# robot.net
KiCad netlist of a schematic drawn in Altium Designer
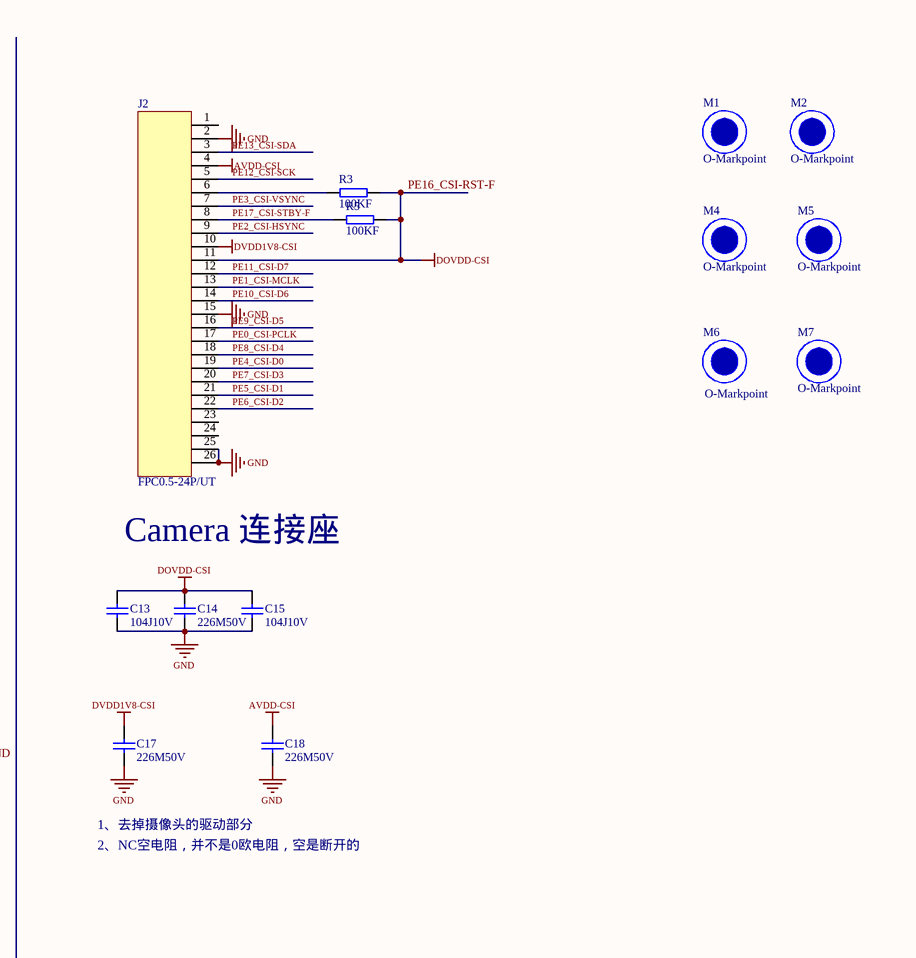
[diagram p0: robot.SchDoc, top right]
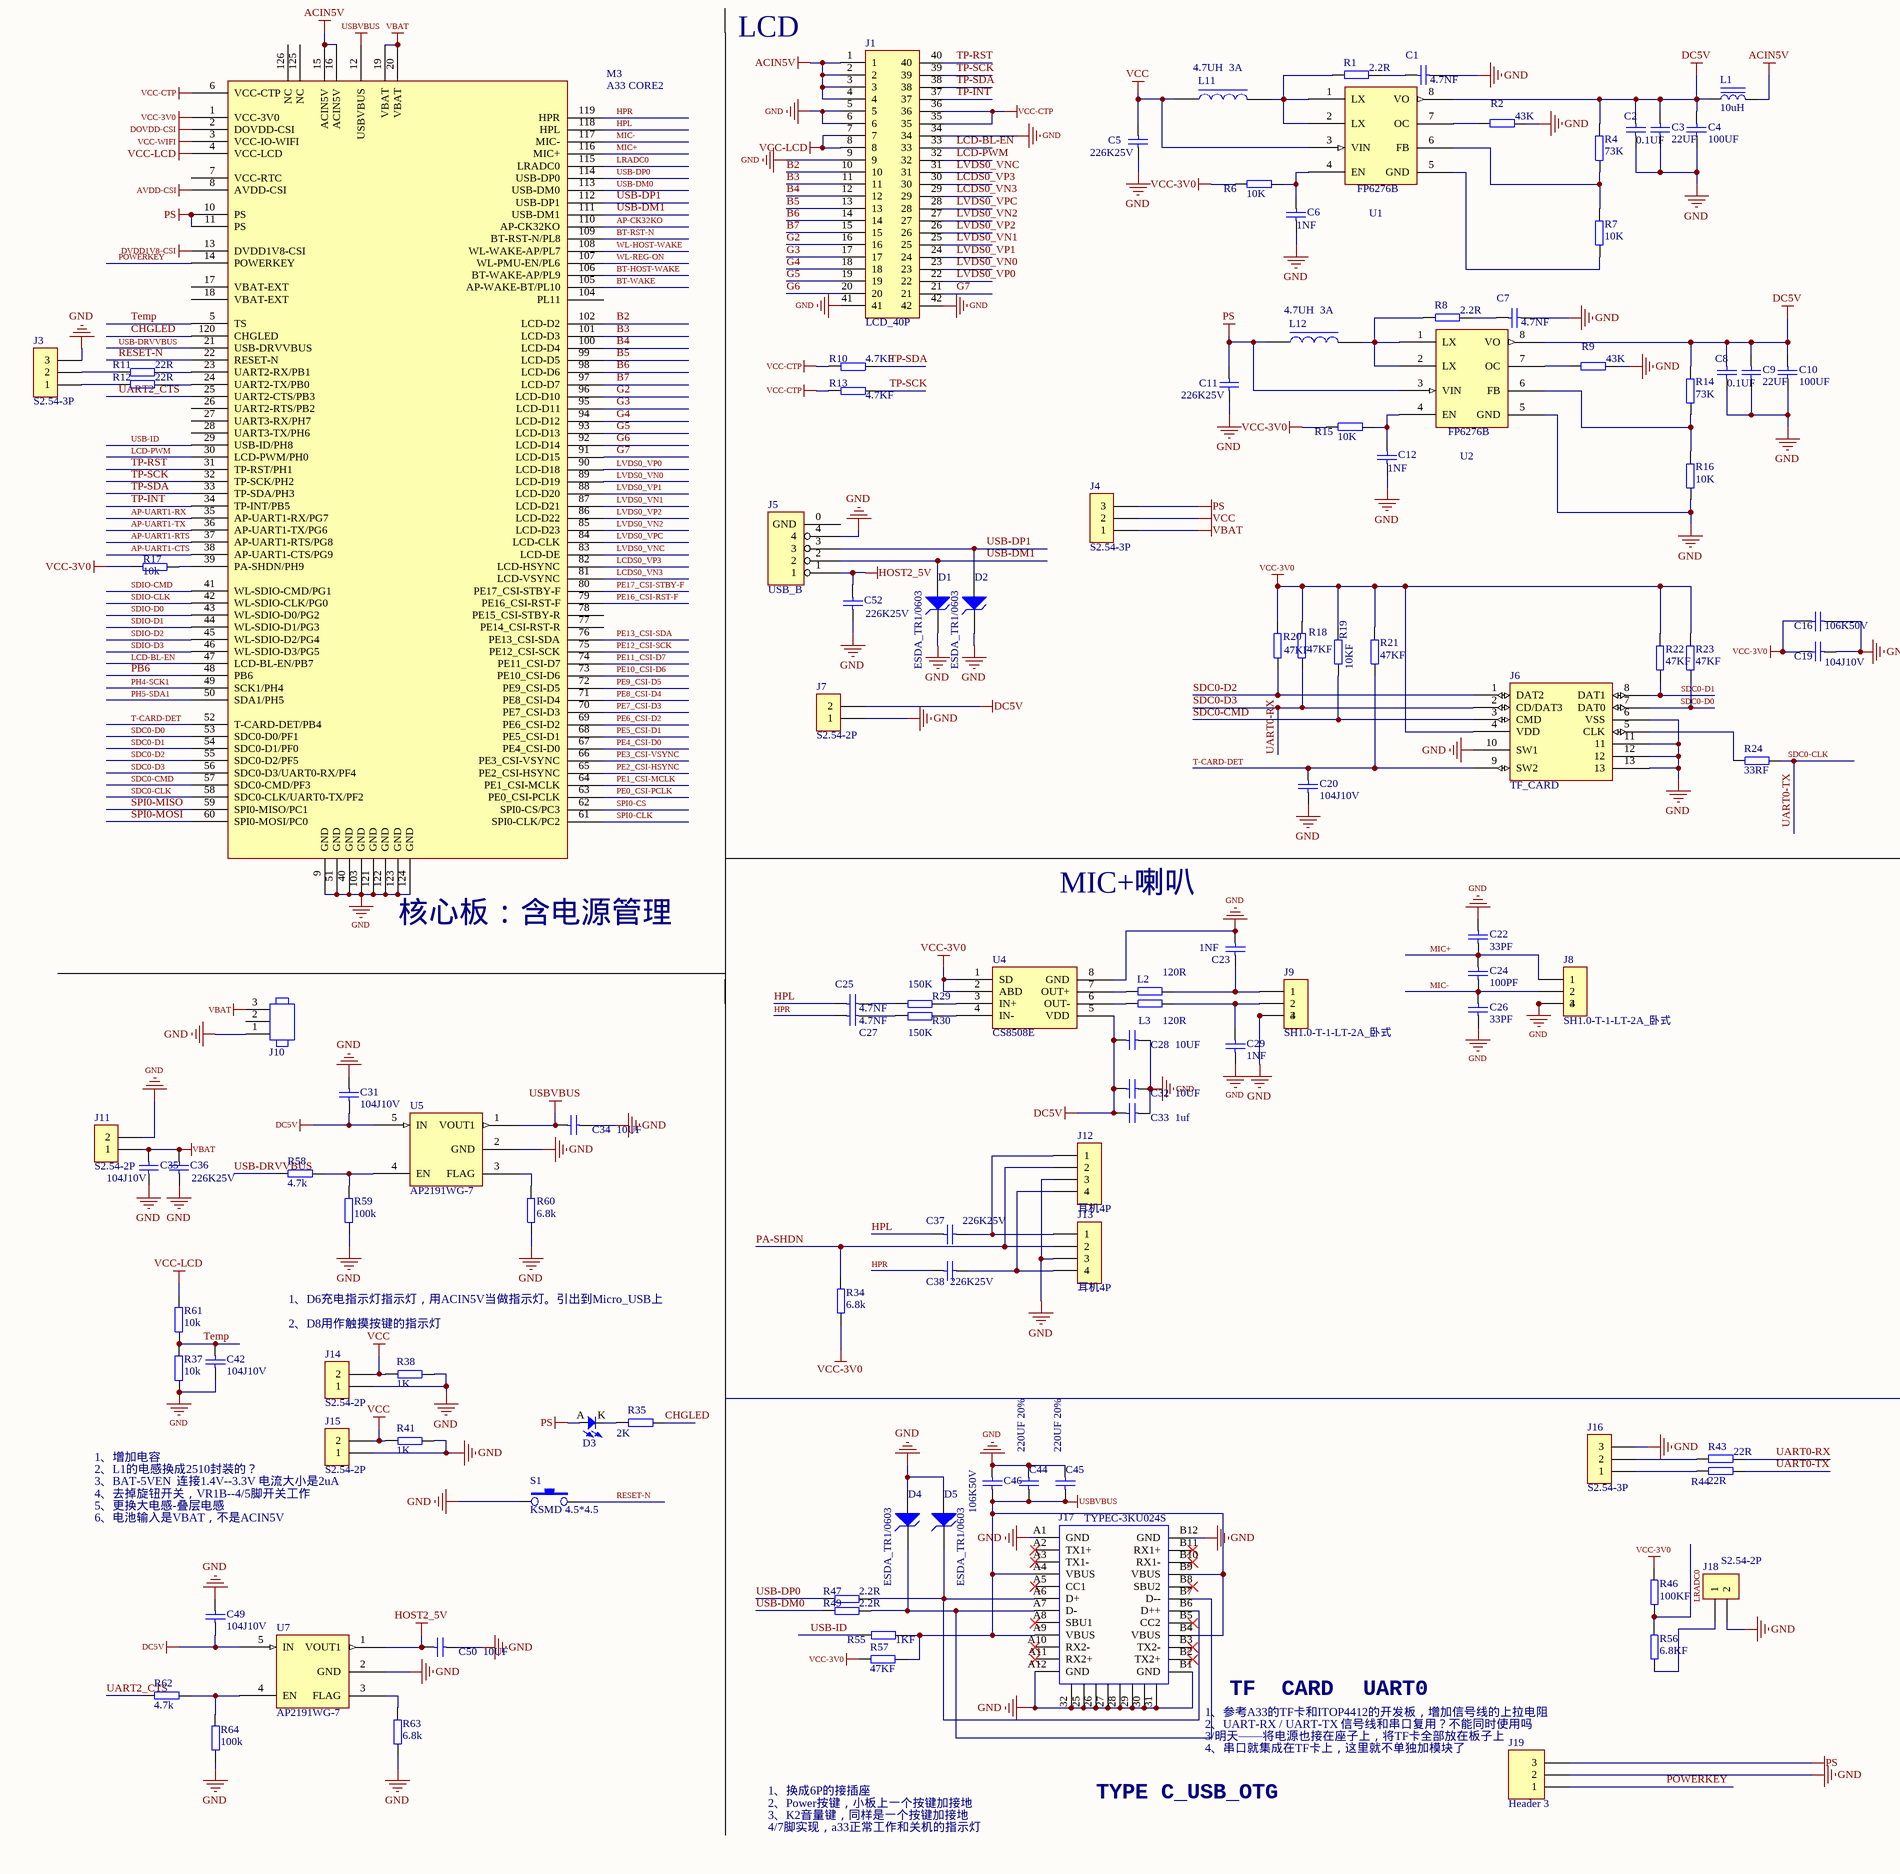
[diagram p1: robot.SchDoc, bottom left]
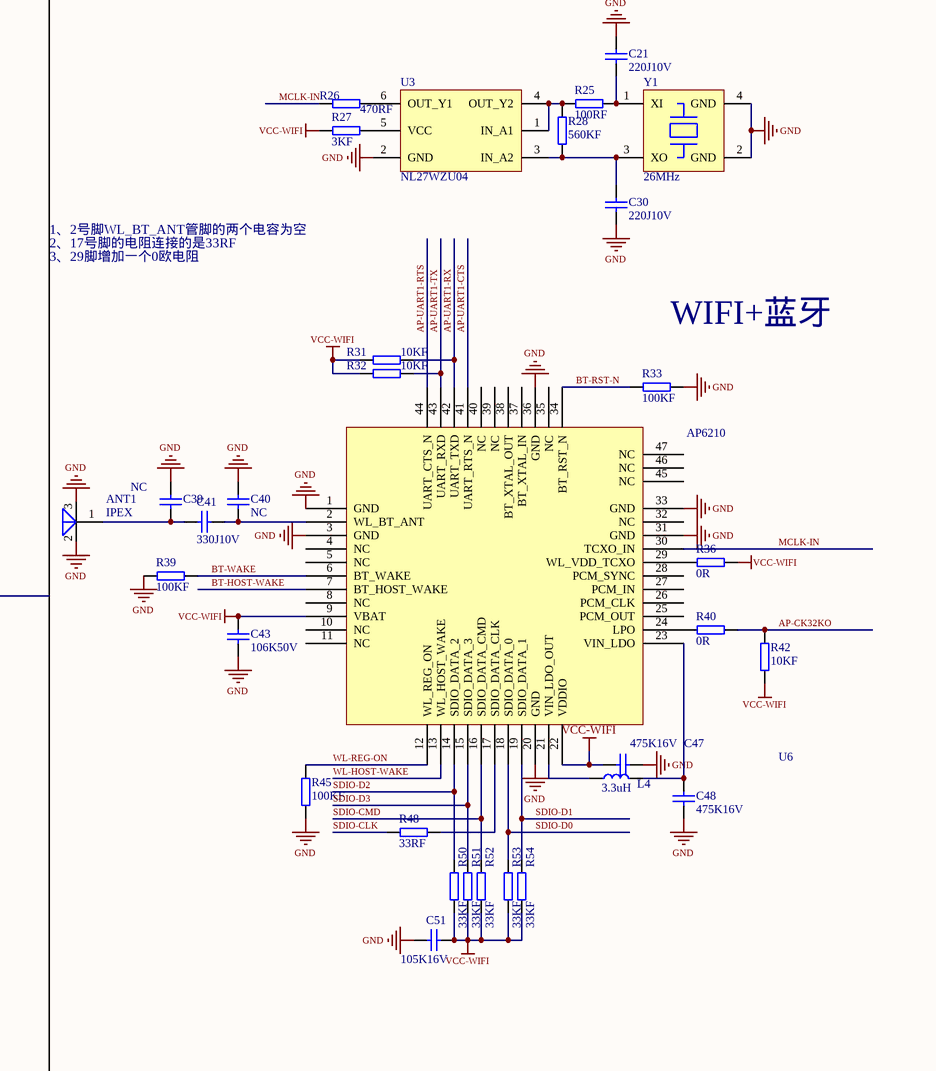
[diagram p2: robot.SchDoc, bottom right]

(export (version "E")
  (design (tool "Eeschema 10.0.6"))
  (components
    (comp (ref "ANT1")
      (value "IPEX")
      (footprint "J-IPEX")
      (description "天线接口IPEX")
      (libsource (lib "Connector") (part "J-IPEX"))
    )
    (comp (ref "C1")
      (value "4.7NF")
      (footprint "C0603")
      (description "贴片电容-陶瓷")
      (libsource (lib "Capacitor") (part "C0603X7R-330J25V"))
    )
    (comp (ref "C2")
      (value "0.1UF")
      (footprint "C0402")
      (description "贴片电容-陶瓷")
      (libsource (lib "AIWAC-bolsterV01") (part "C0402X7R-101J10V"))
    )
    (comp (ref "C3")
      (value "22UF")
      (footprint "C0603")
      (description "贴片电容-陶瓷")
      (libsource (lib "Capacitor") (part "C0603X7R-330J25V"))
    )
    (comp (ref "C4")
      (value "100UF")
      (footprint "CD3X5.3SMD")
      (description "贴片电容-陶瓷")
      (libsource (lib "Capacitor") (part "C0603X7R-330J25V"))
    )
    (comp (ref "C5")
      (value "226K25V")
      (footprint "C0805")
      (description "贴片电容-陶瓷")
      (libsource (lib "Capacitor") (part "C0805X7R-226K25V"))
    )
    (comp (ref "C6")
      (value "1NF")
      (footprint "C0402")
      (description "贴片电容-陶瓷")
      (libsource (lib "AIWAC-bolsterV01") (part "C0402X7R-101J10V"))
    )
    (comp (ref "C7")
      (value "4.7NF")
      (footprint "C0603")
      (description "贴片电容-陶瓷")
      (libsource (lib "Capacitor") (part "C0603X7R-330J25V"))
    )
    (comp (ref "C8")
      (value "0.1UF")
      (footprint "C0402")
      (description "贴片电容-陶瓷")
      (libsource (lib "AIWAC-bolsterV01") (part "C0402X7R-101J10V"))
    )
    (comp (ref "C9")
      (value "22UF")
      (footprint "C0603")
      (description "贴片电容-陶瓷")
      (libsource (lib "Capacitor") (part "C0603X7R-330J25V"))
    )
    (comp (ref "C10")
      (value "100UF")
      (footprint "CD3X5.3SMD")
      (description "贴片电容-陶瓷")
      (libsource (lib "Capacitor") (part "C0603X7R-330J25V"))
    )
    (comp (ref "C11")
      (value "226K25V")
      (footprint "C0805")
      (description "贴片电容-陶瓷")
      (libsource (lib "Capacitor") (part "C0805X7R-226K25V"))
    )
    (comp (ref "C12")
      (value "1NF")
      (footprint "C0402")
      (description "贴片电容-陶瓷")
      (libsource (lib "AIWAC-bolsterV01") (part "C0402X7R-101J10V"))
    )
    (comp (ref "C13")
      (value "104J10V")
      (footprint "C0402")
      (description "贴片电容-陶瓷")
      (libsource (lib "Capacitor") (part "C0402X7R-104J10V"))
    )
    (comp (ref "C14")
      (value "226M50V")
      (footprint "C0805")
      (description "贴片电容-陶瓷")
      (libsource (lib "Capacitor") (part "C0805Y5V-226M50V"))
    )
    (comp (ref "C15")
      (value "104J10V")
      (footprint "C0402")
      (description "贴片电容-陶瓷")
      (libsource (lib "Capacitor") (part "C0402X7R-104J10V"))
    )
    (comp (ref "C16")
      (value "106K50V")
      (footprint "C0603")
      (description "贴片电容-陶瓷")
      (libsource (lib "Capacitor") (part "C0603X7R-106K50V"))
    )
    (comp (ref "C17")
      (value "226M50V")
      (footprint "C0805")
      (description "贴片电容-陶瓷")
      (libsource (lib "Capacitor") (part "C0805Y5V-226M50V"))
    )
    (comp (ref "C18")
      (value "226M50V")
      (footprint "C0805")
      (description "贴片电容-陶瓷")
      (libsource (lib "Capacitor") (part "C0805Y5V-226M50V"))
    )
    (comp (ref "C19")
      (value "104J10V")
      (footprint "C0402")
      (description "贴片电容-陶瓷")
      (libsource (lib "Capacitor") (part "C0402X7R-104J10V"))
    )
    (comp (ref "C20")
      (value "104J10V")
      (footprint "C0402")
      (description "贴片电容-陶瓷")
      (libsource (lib "Capacitor") (part "C0402X7R-104J10V"))
    )
    (comp (ref "C21")
      (value "220J10V")
      (footprint "C0402")
      (description "贴片电容-陶瓷")
      (libsource (lib "Capacitor") (part "C0402X7R-220J10V"))
    )
    (comp (ref "C22")
      (value "33PF")
      (footprint "C0402")
      (description "贴片电容-陶瓷")
      (libsource (lib "Capacitor") (part "C0402X7R-104J10V"))
    )
    (comp (ref "C23")
      (value "1NF")
      (footprint "C0402")
      (description "贴片电容-陶瓷")
      (libsource (lib "Capacitor") (part "C0402X7R-220J10V"))
    )
    (comp (ref "C24")
      (value "100PF")
      (footprint "C0402")
      (description "贴片电容-陶瓷")
      (libsource (lib "Capacitor") (part "C0402X7R-104J10V"))
    )
    (comp (ref "C25")
      (value "4.7NF")
      (footprint "C0603")
      (description "贴片电容-陶瓷")
      (libsource (lib "Capacitor") (part "C0603X7R-330J25V"))
    )
    (comp (ref "C26")
      (value "33PF")
      (footprint "C0402")
      (description "贴片电容-陶瓷")
      (libsource (lib "Capacitor") (part "C0402X7R-104J10V"))
    )
    (comp (ref "C27")
      (value "4.7NF")
      (footprint "C0603")
      (description "贴片电容-陶瓷")
      (libsource (lib "Capacitor") (part "C0603X7R-330J25V"))
    )
    (comp (ref "C28")
      (value "10UF")
      (footprint "C0603")
      (description "贴片电容-陶瓷")
      (libsource (lib "Capacitor") (part "C0603X7R-330J25V"))
    )
    (comp (ref "C29")
      (value "1NF")
      (footprint "C0402")
      (description "贴片电容-陶瓷")
      (libsource (lib "Capacitor") (part "C0402X7R-220J10V"))
    )
    (comp (ref "C30")
      (value "220J10V")
      (footprint "C0402")
      (description "贴片电容-陶瓷")
      (libsource (lib "Capacitor") (part "C0402X7R-220J10V"))
    )
    (comp (ref "C31")
      (value "104J10V")
      (footprint "C0402")
      (description "贴片电容-陶瓷")
      (libsource (lib "Capacitor") (part "C0402X7R-104J10V"))
    )
    (comp (ref "C32")
      (value "10UF")
      (footprint "C0603")
      (description "贴片电容-陶瓷")
      (libsource (lib "Capacitor") (part "C0603X7R-330J25V"))
    )
    (comp (ref "C33")
      (value "1uf")
      (footprint "C0603")
      (description "贴片电容-陶瓷")
      (libsource (lib "Capacitor") (part "C0603X7R-330J25V"))
    )
    (comp (ref "C34")
      (value "10UF")
      (footprint "C0603")
      (description "贴片电容-陶瓷")
      (libsource (lib "Capacitor") (part "C0603X7R-330J25V"))
    )
    (comp (ref "C35")
      (value "104J10V")
      (footprint "C0402")
      (description "贴片电容-陶瓷")
      (libsource (lib "Capacitor") (part "C0402X7R-104J10V"))
    )
    (comp (ref "C36")
      (value "226K25V")
      (footprint "C0805")
      (description "贴片电容-陶瓷")
      (libsource (lib "Capacitor") (part "C0805X7R-226K25V"))
    )
    (comp (ref "C37")
      (value "226K25V")
      (footprint "C0805")
      (description "贴片电容-陶瓷")
      (libsource (lib "Capacitor") (part "C0805X7R-226K25V"))
    )
    (comp (ref "C38")
      (value "226K25V")
      (footprint "C0805")
      (description "贴片电容-陶瓷")
      (libsource (lib "Capacitor") (part "C0805X7R-226K25V"))
    )
    (comp (ref "C39")
      (value "NC")
      (footprint "C0402")
      (description "贴片电容-陶瓷")
      (libsource (lib "Capacitor") (part "C0402X7R-220J10V"))
    )
    (comp (ref "C40")
      (value "NC")
      (footprint "C0402")
      (description "贴片电容-陶瓷")
      (libsource (lib "Capacitor") (part "C0402X7R-220J10V"))
    )
    (comp (ref "C41")
      (value "330J10V")
      (footprint "C0402")
      (description "贴片电容-陶瓷")
      (libsource (lib "Capacitor") (part "C0402X7R-330J10V"))
    )
    (comp (ref "C42")
      (value "104J10V")
      (footprint "C0402")
      (description "贴片电容-陶瓷")
      (libsource (lib "Capacitor") (part "C0402X7R-104J10V"))
    )
    (comp (ref "C43")
      (value "106K50V")
      (footprint "C0603")
      (description "贴片电容-陶瓷")
      (libsource (lib "Capacitor") (part "C0603X7R-106K50V"))
    )
    (comp (ref "C44")
      (value "220UF 20%")
      (footprint "C1206")
      (description "C 1206钽电容 --220UF 10V 3216 A型 有极性电容 3.2mm X 1.6mm")
      (libsource (lib "Capacitor") (part "C1206-A型 极性电容"))
    )
    (comp (ref "C45")
      (value "220UF 20%")
      (footprint "C1206")
      (description "C 1206钽电容 --220UF 10V 3216 A型 有极性电容 3.2mm X 1.6mm")
      (libsource (lib "Capacitor") (part "C1206-A型 极性电容"))
    )
    (comp (ref "C46")
      (value "106K50V")
      (footprint "C0603")
      (description "贴片电容-陶瓷")
      (libsource (lib "Capacitor") (part "C0603X7R-106K50V"))
    )
    (comp (ref "C47")
      (value "475K16V")
      (footprint "C0603")
      (description "贴片电容-陶瓷")
      (libsource (lib "Capacitor") (part "C0603X7R-475K16V"))
    )
    (comp (ref "C48")
      (value "475K16V")
      (footprint "C0603")
      (description "贴片电容-陶瓷")
      (libsource (lib "Capacitor") (part "C0603X7R-475K16V"))
    )
    (comp (ref "C49")
      (value "104J10V")
      (footprint "C0402")
      (description "贴片电容-陶瓷")
      (libsource (lib "Capacitor") (part "C0402X7R-104J10V"))
    )
    (comp (ref "C50")
      (value "10UF")
      (footprint "C0603")
      (description "贴片电容-陶瓷")
      (libsource (lib "Capacitor") (part "C0603X7R-330J25V"))
    )
    (comp (ref "C51")
      (value "105K16V")
      (footprint "C0603")
      (description "贴片电容-陶瓷")
      (libsource (lib "Capacitor") (part "C0603X7R-105K16V"))
    )
    (comp (ref "C52")
      (value "226K25V")
      (footprint "C0805")
      (description "贴片电容-陶瓷")
      (libsource (lib "Capacitor") (part "C0805X7R-226K25V"))
    )
    (comp (ref "D1")
      (value "ESDA_TR1/0603")
      (footprint "HS_0603D")
      (description "Zener Diode")
      (fields (field (name "PUBLISHER") "*"))
      (libsource (lib "1_1") (part "D Zener"))
    )
    (comp (ref "D2")
      (value "ESDA_TR1/0603")
      (footprint "HS_0603D")
      (description "Zener Diode")
      (fields (field (name "PUBLISHER") "*"))
      (libsource (lib "1_1") (part "D Zener"))
    )
    (comp (ref "D3") (value "发光二极管") (footprint "LED 3MM") (libsource (lib "PCB_Project_2") (part "发光二极管")))
    (comp (ref "D4")
      (value "ESDA_TR1/0603")
      (footprint "HS_0603D")
      (description "Zener Diode")
      (fields (field (name "PUBLISHER") "*"))
      (libsource (lib "1_1") (part "D Zener"))
    )
    (comp (ref "D5")
      (value "ESDA_TR1/0603")
      (footprint "HS_0603D")
      (description "Zener Diode")
      (fields (field (name "PUBLISHER") "*"))
      (libsource (lib "1_1") (part "D Zener"))
    )
    (comp (ref "J1") (value "LCD_40P") (footprint "LCD P40") (libsource (lib "Connector") (part "LCD_40P")))
    (comp (ref "J2")
      (value "FPC0.5-24P/UT")
      (footprint "FPC0.5-24P/UT")
      (description "FPC端子")
      (libsource (lib "Connector") (part "J-FPC0.5-24P/UT"))
    )
    (comp (ref "J3")
      (value "S2.54-3P")
      (footprint "S2.54-3P")
      (description "单排排针-直针")
      (libsource (lib "PCB_Project") (part "J-S2.54-3P"))
    )
    (comp (ref "J4")
      (value "S2.54-3P")
      (footprint "S2.54-3P")
      (description "单排排针-直针")
      (libsource (lib "PCB_Project") (part "J-S2.54-3P"))
    )
    (comp (ref "J5")
      (value "USB_B")
      (footprint "PCB1:SMD USB A型")
      (libsource (lib "XU-GENARAL SCH") (part "USB_B"))
    )
    (comp (ref "J6")
      (value "TF_CARD")
      (footprint "SD_CARD_7")
      (description "MS110-C10B-C16")
      (libsource (lib "Connector") (part "TF_CARD"))
    )
    (comp (ref "J7")
      (value "S2.54-2P")
      (footprint "J-SH2.0-T-1-LT-2A_立式")
      (description "单排排针-直针")
      (libsource (lib "Sheye-Connector") (part "J-S2.54-2P"))
    )
    (comp (ref "J8")
      (value "SH1.0-T-1-LT-2A_卧式")
      (footprint "J-SH1.27-2")
      (libsource (lib "Connector") (part "SH1.0-T-1-LT-2A_卧式"))
    )
    (comp (ref "J9")
      (value "SH1.0-T-1-LT-2A_卧式")
      (footprint "J-SH1.27-2")
      (libsource (lib "Connector") (part "SH1.0-T-1-LT-2A_卧式"))
    )
    (comp (ref "J10") (value "SW") (footprint "拨码开关") (libsource (lib "XU-GENARAL SCH") (part "卡槽-3")))
    (comp (ref "J11")
      (value "S2.54-2P")
      (footprint "J-SH2.0-T-1-LT-2A_立式")
      (description "单排排针-直针")
      (libsource (lib "Sheye-Connector") (part "J-S2.54-2P"))
    )
    (comp (ref "J12")
      (value "耳机4P")
      (footprint "耳机接口")
      (description "单排排针-直针")
      (libsource (lib "Connector") (part "J-S2.54-4P"))
    )
    (comp (ref "J13")
      (value "耳机4P")
      (footprint "耳机接口")
      (description "单排排针-直针")
      (libsource (lib "Connector") (part "J-S2.54-4P"))
    )
    (comp (ref "J14")
      (value "S2.54-2P")
      (footprint "J-SH2.0-T-1-LT-2A_立式")
      (description "单排排针-直针")
      (libsource (lib "Sheye-Connector") (part "J-S2.54-2P"))
    )
    (comp (ref "J15")
      (value "S2.54-2P")
      (footprint "J-SH2.0-T-1-LT-2A_立式")
      (description "单排排针-直针")
      (libsource (lib "Sheye-Connector") (part "J-S2.54-2P"))
    )
    (comp (ref "J16")
      (value "S2.54-3P")
      (footprint "S2.54-3P")
      (description "单排排针-直针")
      (libsource (lib "PCB_Project") (part "J-S2.54-3P"))
    )
    (comp (ref "J17")
      (value "TYPEC-3KU024S")
      (footprint "MICRO -TYPE C")
      (description "DIP Switch")
      (fields (field (name "PUBLISHER") "Altium Limited"))
      (libsource (lib "AIWAC-bolsterV01") (part "TYPEC-3KU024S"))
    )
    (comp (ref "J18")
      (value "S2.54-2P")
      (footprint "S2.54-2P")
      (description "单排排针-直针")
      (libsource (lib "PCB_Project") (part "J-S2.54-2P"))
    )
    (comp (ref "J19")
      (value "Header 3")
      (footprint "J-SH1.27 - 3")
      (description "Header, 3-Pin")
      (fields (field (name "PUBLISHER") "Altium Limited"))
      (libsource (lib "蓝牙税控盘V1.1_20171222_oject") (part "Header 3"))
    )
    (comp (ref "L1")
      (value "10uH")
      (footprint "C0603")
      (description "插件电感-工形")
      (libsource (lib "AIWAC-bolsterV01") (part "LI-0608-10uH1A"))
    )
    (comp (ref "L2")
      (value "120R")
      (footprint "R0603")
      (description "贴片电阻-通用")
      (libsource (lib "Resistor") (part "R0603-47KF"))
    )
    (comp (ref "L3")
      (value "120R")
      (footprint "R0603")
      (description "贴片电阻-通用")
      (libsource (lib "Resistor") (part "R0603-47KF"))
    )
    (comp (ref "L4")
      (value "3.3uH")
      (footprint "L0805")
      (description "贴片电感-层叠")
      (libsource (lib "magnetic") (part "L-0805-3.3uH"))
    )
    (comp (ref "L11")
      (value "~")
      (footprint "电感SMD6*6*2.8")
      (fields (field (name "ALTIUM_UNNAMED_1") "4.7UH  3A"))
      (libsource (lib "XU-GENARAL SCH") (part "INDUCTANCE1"))
    )
    (comp (ref "L12")
      (value "~")
      (footprint "电感SMD6*6*2.8")
      (fields (field (name "ALTIUM_UNNAMED_1") "4.7UH  3A"))
      (libsource (lib "XU-GENARAL SCH") (part "INDUCTANCE1"))
    )
    (comp (ref "M1")
      (value "O-Markpoint")
      (footprint "MarkGlobal1")
      (description "MARK点")
      (libsource (lib "Others") (part "O-Markpoint"))
    )
    (comp (ref "M2")
      (value "O-Markpoint")
      (footprint "MarkGlobal1")
      (description "MARK点")
      (libsource (lib "Others") (part "O-Markpoint"))
    )
    (comp (ref "M3")
      (value "A33 CORE2")
      (footprint "机器人:A33-CORE2")
      (libsource (lib "Module") (part "A33 CORE2"))
    )
    (comp (ref "M4")
      (value "O-Markpoint")
      (footprint "MarkGlobal1")
      (description "MARK点")
      (libsource (lib "Others") (part "O-Markpoint"))
    )
    (comp (ref "M5")
      (value "O-Markpoint")
      (footprint "MarkGlobal1")
      (description "MARK点")
      (libsource (lib "Others") (part "O-Markpoint"))
    )
    (comp (ref "M6")
      (value "O-Markpoint")
      (footprint "MarkGlobal1")
      (description "MARK点")
      (libsource (lib "Others") (part "O-Markpoint"))
    )
    (comp (ref "M7")
      (value "O-Markpoint")
      (footprint "MarkGlobal1")
      (description "MARK点")
      (libsource (lib "Others") (part "O-Markpoint"))
    )
    (comp (ref "R1")
      (value "2.2R")
      (footprint "R0603")
      (description "贴片电阻-通用")
      (libsource (lib "Resistor") (part "R0603-2KF"))
    )
    (comp (ref "R2")
      (value "43K")
      (footprint "R0603")
      (description "贴片电阻-通用")
      (libsource (lib "Resistor") (part "R0603-2KF"))
    )
    (comp (ref "R3")
      (value "100KF")
      (footprint "R0603")
      (description "贴片电阻-通用")
      (libsource (lib "Resistor") (part "R0603-100KF"))
    )
    (comp (ref "R4")
      (value "73K")
      (footprint "R0603")
      (description "贴片电阻-通用")
      (libsource (lib "Resistor") (part "R0603-2KF"))
    )
    (comp (ref "R5")
      (value "100KF")
      (footprint "R0603")
      (description "贴片电阻-通用")
      (libsource (lib "Resistor") (part "R0603-100KF"))
    )
    (comp (ref "R6")
      (value "10K")
      (footprint "R0603")
      (description "贴片电阻-通用")
      (libsource (lib "Resistor") (part "R0603-2KF"))
    )
    (comp (ref "R7")
      (value "10K")
      (footprint "R0603")
      (description "贴片电阻-通用")
      (libsource (lib "Resistor") (part "R0603-2KF"))
    )
    (comp (ref "R8")
      (value "2.2R")
      (footprint "R0603")
      (description "贴片电阻-通用")
      (libsource (lib "Resistor") (part "R0603-2KF"))
    )
    (comp (ref "R9")
      (value "43K")
      (footprint "R0603")
      (description "贴片电阻-通用")
      (libsource (lib "Resistor") (part "R0603-2KF"))
    )
    (comp (ref "R10")
      (value "4.7KF")
      (footprint "R0402")
      (description "贴片电阻-通用")
      (libsource (lib "Resistor") (part "R0402-4.7KF"))
    )
    (comp (ref "R11")
      (value "22R")
      (footprint "R0603")
      (description "贴片电阻-通用")
      (libsource (lib "Resistor") (part "R0603-100KF"))
    )
    (comp (ref "R12")
      (value "22R")
      (footprint "R0603")
      (description "贴片电阻-通用")
      (libsource (lib "Resistor") (part "R0603-100KF"))
    )
    (comp (ref "R13")
      (value "4.7KF")
      (footprint "R0402")
      (description "贴片电阻-通用")
      (libsource (lib "Resistor") (part "R0402-4.7KF"))
    )
    (comp (ref "R14")
      (value "73K")
      (footprint "R0603")
      (description "贴片电阻-通用")
      (libsource (lib "Resistor") (part "R0603-2KF"))
    )
    (comp (ref "R15")
      (value "10K")
      (footprint "R0603")
      (description "贴片电阻-通用")
      (libsource (lib "Resistor") (part "R0603-2KF"))
    )
    (comp (ref "R16")
      (value "10K")
      (footprint "R0603")
      (description "贴片电阻-通用")
      (libsource (lib "Resistor") (part "R0603-2KF"))
    )
    (comp (ref "R17")
      (value "10k")
      (footprint "R0603")
      (description "贴片电阻-通用")
      (libsource (lib "Resistor") (part "R0603-10KF"))
    )
    (comp (ref "R18")
      (value "47KF")
      (footprint "R0603")
      (description "贴片电阻-通用")
      (libsource (lib "Resistor") (part "R0603-47KF"))
    )
    (comp (ref "R19")
      (value "10KF")
      (footprint "R0603")
      (description "贴片电阻-通用")
      (libsource (lib "Resistor") (part "R0603-10KF"))
    )
    (comp (ref "R20")
      (value "47KF")
      (footprint "R0603")
      (description "贴片电阻-通用")
      (libsource (lib "Resistor") (part "R0603-47KF"))
    )
    (comp (ref "R21")
      (value "47KF")
      (footprint "R0603")
      (description "贴片电阻-通用")
      (libsource (lib "Resistor") (part "R0603-47KF"))
    )
    (comp (ref "R22")
      (value "47KF")
      (footprint "R0603")
      (description "贴片电阻-通用")
      (libsource (lib "Resistor") (part "R0603-47KF"))
    )
    (comp (ref "R23")
      (value "47KF")
      (footprint "R0603")
      (description "贴片电阻-通用")
      (libsource (lib "Resistor") (part "R0603-47KF"))
    )
    (comp (ref "R24")
      (value "33RF")
      (footprint "R0603")
      (description "贴片电阻-通用")
      (libsource (lib "Resistor") (part "R0603-33RF"))
    )
    (comp (ref "R25")
      (value "100RF")
      (footprint "R0603")
      (description "贴片电阻-通用")
      (libsource (lib "Resistor") (part "R0603-100RF"))
    )
    (comp (ref "R26")
      (value "470RF")
      (footprint "R0603")
      (description "贴片电阻-通用")
      (libsource (lib "Resistor") (part "R0603-470RF"))
    )
    (comp (ref "R27")
      (value "3KF")
      (footprint "R0603")
      (description "贴片电阻-通用")
      (libsource (lib "Resistor") (part "R0603-3KF"))
    )
    (comp (ref "R28")
      (value "560KF")
      (footprint "R0603")
      (description "贴片电阻-通用")
      (libsource (lib "Resistor") (part "R0603-560KF"))
    )
    (comp (ref "R29")
      (value "150K")
      (footprint "R0603")
      (description "贴片电阻-通用")
      (libsource (lib "Resistor") (part "R0603-10KF"))
    )
    (comp (ref "R30")
      (value "150K")
      (footprint "R0603")
      (description "贴片电阻-通用")
      (libsource (lib "Resistor") (part "R0603-10KF"))
    )
    (comp (ref "R31")
      (value "10KF")
      (footprint "R0603")
      (description "贴片电阻-通用")
      (libsource (lib "Resistor") (part "R0603-10KF"))
    )
    (comp (ref "R32")
      (value "10KF")
      (footprint "R0603")
      (description "贴片电阻-通用")
      (libsource (lib "Resistor") (part "R0603-10KF"))
    )
    (comp (ref "R33")
      (value "100KF")
      (footprint "R0603")
      (description "贴片电阻-通用")
      (libsource (lib "Resistor") (part "R0603-100KF"))
    )
    (comp (ref "R34")
      (value "6.8k")
      (footprint "R0402")
      (description "贴片电阻-通用")
      (libsource (lib "PCB_Project_2") (part "R0402-1KF"))
    )
    (comp (ref "R35")
      (value "2K")
      (footprint "R0603")
      (description "贴片电阻-通用")
      (libsource (lib "Resistor") (part "R0603-3KF"))
    )
    (comp (ref "R36")
      (value "0R")
      (footprint "R0603")
      (description "贴片电阻-通用")
      (libsource (lib "Resistor") (part "R0603-0R"))
    )
    (comp (ref "R37")
      (value "10k")
      (footprint "R0402")
      (description "贴片电阻-通用")
      (libsource (lib "PCB_Project_2") (part "R0402-1KF"))
    )
    (comp (ref "R38")
      (value "1K")
      (footprint "R0603")
      (description "贴片电阻-通用")
      (libsource (lib "Resistor") (part "R0603-2KF"))
    )
    (comp (ref "R39")
      (value "100KF")
      (footprint "R0603")
      (description "贴片电阻-通用")
      (libsource (lib "Resistor") (part "R0603-100KF"))
    )
    (comp (ref "R40")
      (value "0R")
      (footprint "R0603")
      (description "贴片电阻-通用")
      (libsource (lib "Resistor") (part "R0603-0R"))
    )
    (comp (ref "R41")
      (value "1K")
      (footprint "R0603")
      (description "贴片电阻-通用")
      (libsource (lib "Resistor") (part "R0603-2KF"))
    )
    (comp (ref "R42")
      (value "10KF")
      (footprint "R0603")
      (description "贴片电阻-通用")
      (libsource (lib "Resistor") (part "R0603-10KF"))
    )
    (comp (ref "R43")
      (value "22R")
      (footprint "R0603")
      (description "贴片电阻-通用")
      (libsource (lib "Resistor") (part "R0603-100KF"))
    )
    (comp (ref "R44")
      (value "22R")
      (footprint "R0603")
      (description "贴片电阻-通用")
      (libsource (lib "Resistor") (part "R0603-100KF"))
    )
    (comp (ref "R45")
      (value "100KF")
      (footprint "R0603")
      (description "贴片电阻-通用")
      (libsource (lib "Resistor") (part "R0603-100KF"))
    )
    (comp (ref "R46")
      (value "100KF")
      (footprint "R0603")
      (description "贴片电阻-通用")
      (libsource (lib "Resistor") (part "R0603-100KF"))
    )
    (comp (ref "R47")
      (value "2.2R")
      (footprint "R0402")
      (description "贴片电阻-通用")
      (libsource (lib "AIWAC-bolsterV01") (part "R0402-1KF"))
    )
    (comp (ref "R48")
      (value "33RF")
      (footprint "R0603")
      (description "贴片电阻-通用")
      (libsource (lib "Resistor") (part "R0603-33RF"))
    )
    (comp (ref "R49")
      (value "2.2R")
      (footprint "R0402")
      (description "贴片电阻-通用")
      (libsource (lib "AIWAC-bolsterV01") (part "R0402-1KF"))
    )
    (comp (ref "R50")
      (value "33KF")
      (footprint "R0603")
      (description "贴片电阻-通用")
      (libsource (lib "Resistor") (part "R0603-33KF"))
    )
    (comp (ref "R51")
      (value "33KF")
      (footprint "R0603")
      (description "贴片电阻-通用")
      (libsource (lib "Resistor") (part "R0603-33KF"))
    )
    (comp (ref "R52")
      (value "33KF")
      (footprint "R0603")
      (description "贴片电阻-通用")
      (libsource (lib "Resistor") (part "R0603-33KF"))
    )
    (comp (ref "R53")
      (value "33KF")
      (footprint "R0603")
      (description "贴片电阻-通用")
      (libsource (lib "Resistor") (part "R0603-33KF"))
    )
    (comp (ref "R54")
      (value "33KF")
      (footprint "R0603")
      (description "贴片电阻-通用")
      (libsource (lib "Resistor") (part "R0603-33KF"))
    )
    (comp (ref "R55")
      (value "1KF")
      (footprint "R0603")
      (description "贴片电阻-通用")
      (libsource (lib "Resistor") (part "R0603-1KF"))
    )
    (comp (ref "R56")
      (value "6.8KF")
      (footprint "R0603")
      (description "贴片电阻-通用")
      (libsource (lib "Resistor") (part "R0603-6.8KF"))
    )
    (comp (ref "R57")
      (value "47KF")
      (footprint "R0603")
      (description "贴片电阻-通用")
      (libsource (lib "Resistor") (part "R0603-47KF"))
    )
    (comp (ref "R58")
      (value "4.7k")
      (footprint "R0402")
      (description "贴片电阻-通用")
      (libsource (lib "PCB_Project_2") (part "R0402-1KF"))
    )
    (comp (ref "R59")
      (value "100k")
      (footprint "R0402")
      (description "贴片电阻-通用")
      (libsource (lib "PCB_Project_2") (part "R0402-1KF"))
    )
    (comp (ref "R60")
      (value "6.8k")
      (footprint "R0402")
      (description "贴片电阻-通用")
      (libsource (lib "PCB_Project_2") (part "R0402-1KF"))
    )
    (comp (ref "R61")
      (value "10k")
      (footprint "R0402")
      (description "贴片电阻-通用")
      (libsource (lib "PCB_Project_2") (part "R0402-1KF"))
    )
    (comp (ref "R62")
      (value "4.7k")
      (footprint "R0402")
      (description "贴片电阻-通用")
      (libsource (lib "PCB_Project_2") (part "R0402-1KF"))
    )
    (comp (ref "R63")
      (value "6.8k")
      (footprint "R0402")
      (description "贴片电阻-通用")
      (libsource (lib "PCB_Project_2") (part "R0402-1KF"))
    )
    (comp (ref "R64")
      (value "100k")
      (footprint "R0402")
      (description "贴片电阻-通用")
      (libsource (lib "PCB_Project_2") (part "R0402-1KF"))
    )
    (comp (ref "S1")
      (value "KSMD 4.5*4.5")
      (footprint "PCB1:侧按4.5*4.5*4.8")
      (description "轻触按键")
      (libsource (lib "Key") (part "S-KSMD6X6-4P"))
    )
    (comp (ref "U1")
      (value "FP6276B")
      (footprint "U-SOP-8N-1")
      (libsource (lib "AIWAC-bolsterV01") (part "FP6267B"))
    )
    (comp (ref "U2")
      (value "FP6276B")
      (footprint "U-SOP-8N-1")
      (libsource (lib "AIWAC-bolsterV01") (part "FP6267B"))
    )
    (comp (ref "U3") (value "NL27WZU04") (footprint "U-TSOP-6") (libsource (lib "IC") (part "NL27WZU04")))
    (comp (ref "U4")
      (value "CS8508E")
      (footprint "U-SOP-8N-1")
      (libsource (lib "PCB_Project_1") (part "CS8508E"))
    )
    (comp (ref "U5")
      (value "AP2191WG-7")
      (footprint "SOT23-5")
      (libsource (lib "AIWAC-bolsterV01") (part "AP2191WG-7"))
    )
    (comp (ref "U6") (value "AP6210") (footprint "机器人:AP6210") (libsource (lib "IC") (part "AP6210")))
    (comp (ref "U7")
      (value "AP2191WG-7")
      (footprint "SOT23-5")
      (libsource (lib "AIWAC-bolsterV01") (part "AP2191WG-7"))
    )
    (comp (ref "Y1")
      (value "26MHz")
      (footprint "Y-CPX-32GA-4P")
      (description "晶振-贴片无源")
      (libsource (lib "Others") (part "YC-26MHz"))
    )
  )
  (nets
    (net (code "2") (name "/AP-CK32KO") (class "Default")
      (node (ref "M3") (pin "110") (pinfunction "AP-CK32KO_110") (pintype "passive"))
      (node (ref "R40") (pin "2") (pinfunction "2_2") (pintype "passive"))
      (node (ref "R42") (pin "2") (pinfunction "2_2") (pintype "passive"))
    )
    (net (code "3") (name "/AP-UART1-CTS") (class "Default")
      (node (ref "M3") (pin "38") (pinfunction "AP-UART1-CTS/PG9_38") (pintype "passive"))
      (node (ref "U6") (pin "41") (pinfunction "UART_RTS_N_41") (pintype "passive"))
    )
    (net (code "4") (name "/AP-UART1-RTS") (class "Default")
      (node (ref "M3") (pin "37") (pinfunction "AP-UART1-RTS/PG8_37") (pintype "passive"))
      (node (ref "U6") (pin "44") (pinfunction "UART_CTS_N_44") (pintype "passive"))
    )
    (net (code "5") (name "/AP-UART1-RX") (class "Default")
      (node (ref "M3") (pin "35") (pinfunction "AP-UART1-RX/PG7_35") (pintype "passive"))
      (node (ref "R31") (pin "2") (pinfunction "2_2") (pintype "passive"))
      (node (ref "U6") (pin "42") (pinfunction "UART_TXD_42") (pintype "passive"))
    )
    (net (code "6") (name "/AP-UART1-TX") (class "Default")
      (node (ref "M3") (pin "36") (pinfunction "AP-UART1-TX/PG6_36") (pintype "passive"))
      (node (ref "R32") (pin "2") (pinfunction "2_2") (pintype "passive"))
      (node (ref "U6") (pin "43") (pinfunction "UART_RXD_43") (pintype "passive"))
    )
    (net (code "7") (name "/B2") (class "Default")
      (node (ref "J1") (pin "10") (pinfunction "10_10") (pintype "passive"))
      (node (ref "M3") (pin "102") (pinfunction "LCD-D2_102") (pintype "passive"))
    )
    (net (code "8") (name "/B3") (class "Default")
      (node (ref "J1") (pin "11") (pinfunction "11_11") (pintype "passive"))
      (node (ref "M3") (pin "101") (pinfunction "LCD-D3_101") (pintype "passive"))
    )
    (net (code "9") (name "/B4") (class "Default")
      (node (ref "J1") (pin "12") (pinfunction "12_12") (pintype "passive"))
      (node (ref "M3") (pin "100") (pinfunction "LCD-D4_100") (pintype "passive"))
    )
    (net (code "10") (name "/B5") (class "Default")
      (node (ref "J1") (pin "13") (pinfunction "13_13") (pintype "passive"))
      (node (ref "M3") (pin "99") (pinfunction "LCD-D5_99") (pintype "passive"))
    )
    (net (code "11") (name "/B6") (class "Default")
      (node (ref "J1") (pin "14") (pinfunction "14_14") (pintype "passive"))
      (node (ref "M3") (pin "98") (pinfunction "LCD-D6_98") (pintype "passive"))
    )
    (net (code "12") (name "/B7") (class "Default")
      (node (ref "J1") (pin "15") (pinfunction "15_15") (pintype "passive"))
      (node (ref "M3") (pin "97") (pinfunction "LCD-D7_97") (pintype "passive"))
    )
    (net (code "13") (name "/BT-HOST-WAKE") (class "Default")
      (node (ref "M3") (pin "106") (pinfunction "BT-WAKE-AP/PL9_106") (pintype "passive"))
      (node (ref "U6") (pin "7") (pinfunction "BT_HOST_WAKE_7") (pintype "passive"))
    )
    (net (code "14") (name "/BT-RST-N") (class "Default")
      (node (ref "M3") (pin "109") (pinfunction "BT-RST-N/PL8_109") (pintype "passive"))
      (node (ref "R33") (pin "1") (pinfunction "1_1") (pintype "passive"))
      (node (ref "U6") (pin "34") (pinfunction "BT_RST_N_34") (pintype "passive"))
    )
    (net (code "15") (name "/BT-WAKE") (class "Default")
      (node (ref "M3") (pin "105") (pinfunction "AP-WAKE-BT/PL10_105") (pintype "passive"))
      (node (ref "R39") (pin "1") (pinfunction "1_1") (pintype "passive"))
      (node (ref "U6") (pin "6") (pinfunction "BT_WAKE_6") (pintype "passive"))
    )
    (net (code "16") (name "/CHGLED") (class "Default")
      (node (ref "M3") (pin "120") (pinfunction "CHGLED_120") (pintype "passive"))
      (node (ref "R35") (pin "2") (pinfunction "2_2") (pintype "passive"))
    )
    (net (code "17") (name "/G2") (class "Default")
      (node (ref "J1") (pin "16") (pinfunction "16_16") (pintype "passive"))
      (node (ref "M3") (pin "96") (pinfunction "LCD-D10_96") (pintype "passive"))
    )
    (net (code "18") (name "/G3") (class "Default")
      (node (ref "J1") (pin "17") (pinfunction "17_17") (pintype "passive"))
      (node (ref "M3") (pin "95") (pinfunction "LCD-D11_95") (pintype "passive"))
    )
    (net (code "19") (name "/G4") (class "Default")
      (node (ref "J1") (pin "18") (pinfunction "18_18") (pintype "passive"))
      (node (ref "M3") (pin "94") (pinfunction "LCD-D12_94") (pintype "passive"))
    )
    (net (code "20") (name "/G5") (class "Default")
      (node (ref "J1") (pin "19") (pinfunction "19_19") (pintype "passive"))
      (node (ref "M3") (pin "93") (pinfunction "LCD-D13_93") (pintype "passive"))
    )
    (net (code "21") (name "/G6") (class "Default")
      (node (ref "J1") (pin "20") (pinfunction "20_20") (pintype "passive"))
      (node (ref "M3") (pin "92") (pinfunction "LCD-D14_92") (pintype "passive"))
    )
    (net (code "22") (name "/G7") (class "Default")
      (node (ref "J1") (pin "21") (pinfunction "21_21") (pintype "passive"))
      (node (ref "M3") (pin "91") (pinfunction "LCD-D15_91") (pintype "passive"))
    )
    (net (code "23") (name "/HPL") (class "Default")
      (node (ref "C25") (pin "1") (pinfunction "1_1") (pintype "passive"))
      (node (ref "C37") (pin "1") (pinfunction "1_1") (pintype "passive"))
      (node (ref "M3") (pin "118") (pinfunction "HPL_118") (pintype "passive"))
    )
    (net (code "24") (name "/HPR") (class "Default")
      (node (ref "C27") (pin "1") (pinfunction "1_1") (pintype "passive"))
      (node (ref "C38") (pin "1") (pinfunction "1_1") (pintype "passive"))
      (node (ref "M3") (pin "119") (pinfunction "HPR_119") (pintype "passive"))
    )
    (net (code "25") (name "/LCD-BL-EN") (class "Default")
      (node (ref "J1") (pin "33") (pinfunction "33_33") (pintype "passive"))
      (node (ref "M3") (pin "47") (pinfunction "LCD-BL-EN/PB7_47") (pintype "passive"))
    )
    (net (code "26") (name "/LCD-PWM") (class "Default")
      (node (ref "J1") (pin "32") (pinfunction "32_32") (pintype "passive"))
      (node (ref "M3") (pin "30") (pinfunction "LCD-PWM/PH0_30") (pintype "passive"))
    )
    (net (code "27") (name "/LCDS0_VN3") (class "Default")
      (node (ref "J1") (pin "29") (pinfunction "29_29") (pintype "passive"))
      (node (ref "M3") (pin "81") (pinfunction "LCD-VSYNC_81") (pintype "passive"))
    )
    (net (code "28") (name "/LCDS0_VP3") (class "Default")
      (node (ref "J1") (pin "30") (pinfunction "30_30") (pintype "passive"))
      (node (ref "M3") (pin "82") (pinfunction "LCD-HSYNC_82") (pintype "passive"))
    )
    (net (code "29") (name "/LRADC0") (class "Default")
      (node (ref "M3") (pin "115") (pinfunction "LRADC0_115") (pintype "passive"))
      (node (ref "R46") (pin "2") (pinfunction "2_2") (pintype "passive"))
      (node (ref "R56") (pin "1") (pinfunction "1_1") (pintype "passive"))
    )
    (net (code "30") (name "/LVDS0_VN0") (class "Default")
      (node (ref "J1") (pin "23") (pinfunction "23_23") (pintype "passive"))
      (node (ref "M3") (pin "89") (pinfunction "LCD-D19_89") (pintype "passive"))
    )
    (net (code "31") (name "/LVDS0_VN1") (class "Default")
      (node (ref "J1") (pin "25") (pinfunction "25_25") (pintype "passive"))
      (node (ref "M3") (pin "87") (pinfunction "LCD-D21_87") (pintype "passive"))
    )
    (net (code "32") (name "/LVDS0_VN2") (class "Default")
      (node (ref "J1") (pin "27") (pinfunction "27_27") (pintype "passive"))
      (node (ref "M3") (pin "85") (pinfunction "LCD-D23_85") (pintype "passive"))
    )
    (net (code "33") (name "/LVDS0_VNC") (class "Default")
      (node (ref "J1") (pin "31") (pinfunction "31_31") (pintype "passive"))
      (node (ref "M3") (pin "83") (pinfunction "LCD-DE_83") (pintype "passive"))
    )
    (net (code "34") (name "/LVDS0_VP0") (class "Default")
      (node (ref "J1") (pin "22") (pinfunction "22_22") (pintype "passive"))
      (node (ref "M3") (pin "90") (pinfunction "LCD-D18_90") (pintype "passive"))
    )
    (net (code "35") (name "/LVDS0_VP1") (class "Default")
      (node (ref "J1") (pin "24") (pinfunction "24_24") (pintype "passive"))
      (node (ref "M3") (pin "88") (pinfunction "LCD-D20_88") (pintype "passive"))
    )
    (net (code "36") (name "/LVDS0_VP2") (class "Default")
      (node (ref "J1") (pin "26") (pinfunction "26_26") (pintype "passive"))
      (node (ref "M3") (pin "86") (pinfunction "LCD-D22_86") (pintype "passive"))
    )
    (net (code "37") (name "/LVDS0_VPC") (class "Default")
      (node (ref "J1") (pin "28") (pinfunction "28_28") (pintype "passive"))
      (node (ref "M3") (pin "84") (pinfunction "LCD-CLK_84") (pintype "passive"))
    )
    (net (code "38") (name "/MCLK-IN") (class "Default")
      (node (ref "R26") (pin "1") (pinfunction "1_1") (pintype "passive"))
      (node (ref "U6") (pin "30") (pinfunction "TCXO_IN_30") (pintype "passive"))
    )
    (net (code "39") (name "/MIC+") (class "Default")
      (node (ref "C22") (pin "2") (pinfunction "2_2") (pintype "passive"))
      (node (ref "C24") (pin "1") (pinfunction "1_1") (pintype "passive"))
      (node (ref "J8") (pin "1") (pinfunction "1_1") (pintype "passive"))
      (node (ref "M3") (pin "116") (pinfunction "MIC+_116") (pintype "passive"))
    )
    (net (code "40") (name "/MIC-") (class "Default")
      (node (ref "C24") (pin "2") (pinfunction "2_2") (pintype "passive"))
      (node (ref "C26") (pin "1") (pinfunction "1_1") (pintype "passive"))
      (node (ref "J8") (pin "2") (pinfunction "2_2") (pintype "passive"))
      (node (ref "M3") (pin "117") (pinfunction "MIC-_117") (pintype "passive"))
    )
    (net (code "41") (name "/PA-SHDN") (class "Default")
      (node (ref "J12") (pin "2") (pinfunction "2_2") (pintype "passive"))
      (node (ref "J13") (pin "2") (pinfunction "2_2") (pintype "passive"))
      (node (ref "R34") (pin "1") (pinfunction "1_1") (pintype "passive"))
    )
    (net (code "42") (name "/PB6") (class "Default")
      (node (ref "M3") (pin "48") (pinfunction "PB6_48") (pintype "passive"))
    )
    (net (code "43") (name "/PE0_CSI-PCLK") (class "Default")
      (node (ref "J2") (pin "17") (pinfunction "17_17") (pintype "passive"))
      (node (ref "M3") (pin "63") (pinfunction "PE0_CSI-PCLK_63") (pintype "passive"))
    )
    (net (code "44") (name "/PE1_CSI-MCLK") (class "Default")
      (node (ref "J2") (pin "13") (pinfunction "13_13") (pintype "passive"))
      (node (ref "M3") (pin "64") (pinfunction "PE1_CSI-MCLK_64") (pintype "passive"))
    )
    (net (code "45") (name "/PE2_CSI-HSYNC") (class "Default")
      (node (ref "J2") (pin "9") (pinfunction "9_9") (pintype "passive"))
      (node (ref "M3") (pin "65") (pinfunction "PE2_CSI-HSYNC_65") (pintype "passive"))
    )
    (net (code "46") (name "/PE3_CSI-VSYNC") (class "Default")
      (node (ref "J2") (pin "7") (pinfunction "7_7") (pintype "passive"))
      (node (ref "M3") (pin "66") (pinfunction "PE3_CSI-VSYNC_66") (pintype "passive"))
    )
    (net (code "47") (name "/PE4_CSI-D0") (class "Default")
      (node (ref "J2") (pin "19") (pinfunction "19_19") (pintype "passive"))
      (node (ref "M3") (pin "67") (pinfunction "PE4_CSI-D0_67") (pintype "passive"))
    )
    (net (code "48") (name "/PE5_CSI-D1") (class "Default")
      (node (ref "J2") (pin "21") (pinfunction "21_21") (pintype "passive"))
      (node (ref "M3") (pin "68") (pinfunction "PE5_CSI-D1_68") (pintype "passive"))
    )
    (net (code "49") (name "/PE6_CSI-D2") (class "Default")
      (node (ref "J2") (pin "22") (pinfunction "22_22") (pintype "passive"))
      (node (ref "M3") (pin "69") (pinfunction "PE6_CSI-D2_69") (pintype "passive"))
    )
    (net (code "50") (name "/PE7_CSI-D3") (class "Default")
      (node (ref "J2") (pin "20") (pinfunction "20_20") (pintype "passive"))
      (node (ref "M3") (pin "70") (pinfunction "PE7_CSI-D3_70") (pintype "passive"))
    )
    (net (code "51") (name "/PE8_CSI-D4") (class "Default")
      (node (ref "J2") (pin "18") (pinfunction "18_18") (pintype "passive"))
      (node (ref "M3") (pin "71") (pinfunction "PE8_CSI-D4_71") (pintype "passive"))
    )
    (net (code "52") (name "/PE9_CSI-D5") (class "Default")
      (node (ref "J2") (pin "16") (pinfunction "16_16") (pintype "passive"))
      (node (ref "M3") (pin "72") (pinfunction "PE9_CSI-D5_72") (pintype "passive"))
    )
    (net (code "53") (name "/PE10_CSI-D6") (class "Default")
      (node (ref "J2") (pin "14") (pinfunction "14_14") (pintype "passive"))
      (node (ref "M3") (pin "73") (pinfunction "PE10_CSI-D6_73") (pintype "passive"))
    )
    (net (code "54") (name "/PE11_CSI-D7") (class "Default")
      (node (ref "J2") (pin "12") (pinfunction "12_12") (pintype "passive"))
      (node (ref "M3") (pin "74") (pinfunction "PE11_CSI-D7_74") (pintype "passive"))
    )
    (net (code "55") (name "/PE12_CSI-SCK") (class "Default")
      (node (ref "J2") (pin "5") (pinfunction "5_5") (pintype "passive"))
      (node (ref "M3") (pin "75") (pinfunction "PE12_CSI-SCK_75") (pintype "passive"))
    )
    (net (code "56") (name "/PE13_CSI-SDA") (class "Default")
      (node (ref "J2") (pin "3") (pinfunction "3_3") (pintype "passive"))
      (node (ref "M3") (pin "76") (pinfunction "PE13_CSI-SDA_76") (pintype "passive"))
    )
    (net (code "57") (name "/PE17_CSI-STBY-F") (class "Default")
      (node (ref "J2") (pin "8") (pinfunction "8_8") (pintype "passive"))
      (node (ref "M3") (pin "80") (pinfunction "PE17_CSI-STBY-F_80") (pintype "passive"))
      (node (ref "R5") (pin "1") (pinfunction "1_1") (pintype "passive"))
    )
    (net (code "58") (name "/PH4-SCK1") (class "Default")
      (node (ref "M3") (pin "49") (pinfunction "SCK1/PH4_49") (pintype "passive"))
    )
    (net (code "59") (name "/PH5-SDA1") (class "Default")
      (node (ref "M3") (pin "50") (pinfunction "SDA1/PH5_50") (pintype "passive"))
    )
    (net (code "60") (name "/POWERKEY") (class "Default")
      (node (ref "J19") (pin "1") (pinfunction "1_1") (pintype "passive"))
      (node (ref "M3") (pin "14") (pinfunction "POWERKEY_14") (pintype "passive"))
    )
    (net (code "61") (name "/RESET-N") (class "Default")
      (node (ref "M3") (pin "22") (pinfunction "RESET-N_22") (pintype "passive"))
      (node (ref "S1") (pin "2") (pinfunction "2_2") (pintype "passive"))
    )
    (net (code "62") (name "/SDC0-CLK") (class "Default")
      (node (ref "M3") (pin "58") (pinfunction "SDC0-CLK/UART0-TX/PF2_58") (pintype "passive"))
      (node (ref "R24") (pin "1") (pinfunction "1_1") (pintype "passive"))
      (node (ref "R44") (pin "1") (pinfunction "1_1") (pintype "passive"))
    )
    (net (code "63") (name "/SDC0-CMD") (class "Default")
      (node (ref "J6") (pin "3") (pinfunction "CMD_3") (pintype "bidirectional"))
      (node (ref "M3") (pin "57") (pinfunction "SDC0-CMD/PF3_57") (pintype "passive"))
      (node (ref "R19") (pin "1") (pinfunction "1_1") (pintype "passive"))
    )
    (net (code "64") (name "/SDC0-D0") (class "Default")
      (node (ref "J6") (pin "7") (pinfunction "DAT0_7") (pintype "bidirectional"))
      (node (ref "M3") (pin "53") (pinfunction "SDC0-D0/PF1_53") (pintype "passive"))
      (node (ref "R23") (pin "1") (pinfunction "1_1") (pintype "passive"))
    )
    (net (code "65") (name "/SDC0-D1") (class "Default")
      (node (ref "J6") (pin "8") (pinfunction "DAT1_8") (pintype "bidirectional"))
      (node (ref "M3") (pin "54") (pinfunction "SDC0-D1/PF0_54") (pintype "passive"))
      (node (ref "R22") (pin "1") (pinfunction "1_1") (pintype "passive"))
    )
    (net (code "66") (name "/SDC0-D2") (class "Default")
      (node (ref "J6") (pin "1") (pinfunction "DAT2_1") (pintype "bidirectional"))
      (node (ref "M3") (pin "55") (pinfunction "SDC0-D2/PF5_55") (pintype "passive"))
      (node (ref "R20") (pin "1") (pinfunction "1_1") (pintype "passive"))
    )
    (net (code "67") (name "/SDC0-D3") (class "Default")
      (node (ref "J6") (pin "2") (pinfunction "CD/DAT3_2") (pintype "bidirectional"))
      (node (ref "M3") (pin "56") (pinfunction "SDC0-D3/UART0-RX/PF4_56") (pintype "passive"))
      (node (ref "R18") (pin "1") (pinfunction "1_1") (pintype "passive"))
      (node (ref "R43") (pin "1") (pinfunction "1_1") (pintype "passive"))
    )
    (net (code "68") (name "/SDIO-CLK") (class "Default")
      (node (ref "M3") (pin "42") (pinfunction "WL-SDIO-CLK/PG0_42") (pintype "passive"))
      (node (ref "R48") (pin "2") (pinfunction "2_2") (pintype "passive"))
    )
    (net (code "69") (name "/SDIO-CMD") (class "Default")
      (node (ref "M3") (pin "41") (pinfunction "WL-SDIO-CMD/PG1_41") (pintype "passive"))
      (node (ref "R52") (pin "2") (pinfunction "2_2") (pintype "passive"))
      (node (ref "U6") (pin "16") (pinfunction "SDIO_DATA_CMD_16") (pintype "passive"))
    )
    (net (code "70") (name "/SDIO-D0") (class "Default")
      (node (ref "M3") (pin "43") (pinfunction "WL-SDIO-D0/PG2_43") (pintype "passive"))
      (node (ref "R53") (pin "2") (pinfunction "2_2") (pintype "passive"))
      (node (ref "U6") (pin "18") (pinfunction "SDIO_DATA_0_18") (pintype "passive"))
    )
    (net (code "71") (name "/SDIO-D1") (class "Default")
      (node (ref "M3") (pin "44") (pinfunction "WL-SDIO-D1/PG3_44") (pintype "passive"))
      (node (ref "R54") (pin "2") (pinfunction "2_2") (pintype "passive"))
      (node (ref "U6") (pin "19") (pinfunction "SDIO_DATA_1_19") (pintype "passive"))
    )
    (net (code "72") (name "/SDIO-D2") (class "Default")
      (node (ref "M3") (pin "45") (pinfunction "WL-SDIO-D2/PG4_45") (pintype "passive"))
      (node (ref "R50") (pin "2") (pinfunction "2_2") (pintype "passive"))
      (node (ref "U6") (pin "14") (pinfunction "SDIO_DATA_2_14") (pintype "passive"))
    )
    (net (code "73") (name "/SDIO-D3") (class "Default")
      (node (ref "M3") (pin "46") (pinfunction "WL-SDIO-D3/PG5_46") (pintype "passive"))
      (node (ref "R51") (pin "2") (pinfunction "2_2") (pintype "passive"))
      (node (ref "U6") (pin "15") (pinfunction "SDIO_DATA_3_15") (pintype "passive"))
    )
    (net (code "74") (name "/SPI0-CLK") (class "Default")
      (node (ref "M3") (pin "61") (pinfunction "SPI0-CLK/PC2_61") (pintype "passive"))
    )
    (net (code "75") (name "/SPI0-CS") (class "Default")
      (node (ref "M3") (pin "62") (pinfunction "SPI0-CS/PC3_62") (pintype "passive"))
    )
    (net (code "76") (name "/SPI0-MISO") (class "Default")
      (node (ref "M3") (pin "59") (pinfunction "SPI0-MISO/PC1_59") (pintype "passive"))
    )
    (net (code "77") (name "/SPI0-MOSI") (class "Default")
      (node (ref "M3") (pin "60") (pinfunction "SPI0-MOSI/PC0_60") (pintype "passive"))
    )
    (net (code "78") (name "/T-CARD-DET") (class "Default")
      (node (ref "C20") (pin "1") (pinfunction "1_1") (pintype "passive"))
      (node (ref "J6") (pin "9") (pinfunction "SW2_9") (pintype "bidirectional"))
      (node (ref "M3") (pin "52") (pinfunction "T-CARD-DET/PB4_52") (pintype "passive"))
      (node (ref "R21") (pin "1") (pinfunction "1_1") (pintype "passive"))
    )
    (net (code "79") (name "/TP-INT") (class "Default")
      (node (ref "J1") (pin "37") (pinfunction "37_37") (pintype "passive"))
      (node (ref "M3") (pin "34") (pinfunction "TP-INT/PB5_34") (pintype "passive"))
    )
    (net (code "80") (name "/TP-RST") (class "Default")
      (node (ref "J1") (pin "40") (pinfunction "40_40") (pintype "passive"))
      (node (ref "M3") (pin "31") (pinfunction "TP-RST/PH1_31") (pintype "passive"))
    )
    (net (code "81") (name "/TP-SCK") (class "Default")
      (node (ref "J1") (pin "39") (pinfunction "39_39") (pintype "passive"))
      (node (ref "M3") (pin "32") (pinfunction "TP-SCK/PH2_32") (pintype "passive"))
      (node (ref "R13") (pin "2") (pinfunction "2_2") (pintype "passive"))
    )
    (net (code "82") (name "/TP-SDA") (class "Default")
      (node (ref "J1") (pin "38") (pinfunction "38_38") (pintype "passive"))
      (node (ref "M3") (pin "33") (pinfunction "TP-SDA/PH3_33") (pintype "passive"))
      (node (ref "R10") (pin "2") (pinfunction "2_2") (pintype "passive"))
    )
    (net (code "83") (name "/Temp") (class "Default")
      (node (ref "C42") (pin "1") (pinfunction "1_1") (pintype "passive"))
      (node (ref "M3") (pin "5") (pinfunction "TS_5") (pintype "passive"))
      (node (ref "R37") (pin "2") (pinfunction "2_2") (pintype "passive"))
      (node (ref "R61") (pin "1") (pinfunction "1_1") (pintype "passive"))
    )
    (net (code "84") (name "/UART2_CTS") (class "Default")
      (node (ref "M3") (pin "25") (pinfunction "UART2-CTS/PB3_25") (pintype "passive"))
      (node (ref "R62") (pin "2") (pinfunction "2_2") (pintype "passive"))
    )
    (net (code "85") (name "/USB-DM0") (class "Default")
      (node (ref "M3") (pin "113") (pinfunction "USB-DM0_113") (pintype "passive"))
      (node (ref "R49") (pin "1") (pinfunction "1_1") (pintype "passive"))
    )
    (net (code "86") (name "/USB-DM1") (class "Default")
      (node (ref "D1") (pin "1") (pinfunction "A_1") (pintype "passive"))
      (node (ref "J5") (pin "2") (pinfunction "2_2") (pintype "passive"))
      (node (ref "M3") (pin "111") (pinfunction "USB-DM1_111") (pintype "passive"))
    )
    (net (code "87") (name "/USB-DP0") (class "Default")
      (node (ref "M3") (pin "114") (pinfunction "USB-DP0_114") (pintype "passive"))
      (node (ref "R47") (pin "1") (pinfunction "1_1") (pintype "passive"))
    )
    (net (code "88") (name "/USB-DP1") (class "Default")
      (node (ref "D2") (pin "1") (pinfunction "A_1") (pintype "passive"))
      (node (ref "J5") (pin "3") (pinfunction "3_3") (pintype "passive"))
      (node (ref "M3") (pin "112") (pinfunction "USB-DP1_112") (pintype "passive"))
    )
    (net (code "89") (name "/USB-DRVVBUS") (class "Default")
      (node (ref "M3") (pin "21") (pinfunction "USB-DRVVBUS_21") (pintype "passive"))
      (node (ref "R58") (pin "2") (pinfunction "2_2") (pintype "passive"))
    )
    (net (code "90") (name "/USB-ID") (class "Default")
      (node (ref "M3") (pin "29") (pinfunction "USB-ID/PH8_29") (pintype "passive"))
      (node (ref "R55") (pin "1") (pinfunction "1_1") (pintype "passive"))
    )
    (net (code "91") (name "/WL-HOST-WAKE") (class "Default")
      (node (ref "M3") (pin "108") (pinfunction "WL-WAKE-AP/PL7_108") (pintype "passive"))
      (node (ref "U6") (pin "13") (pinfunction "WL_HOST_WAKE_13") (pintype "passive"))
    )
    (net (code "92") (name "/WL-REG-ON") (class "Default")
      (node (ref "M3") (pin "107") (pinfunction "WL-PMU-EN/PL6_107") (pintype "passive"))
      (node (ref "R45") (pin "1") (pinfunction "1_1") (pintype "passive"))
      (node (ref "U6") (pin "12") (pinfunction "WL_REG_ON_12") (pintype "passive"))
    )
    (net (code "93") (name "ACIN5V") (class "Default")
      (node (ref "J1") (pin "1") (pinfunction "1_1") (pintype "passive"))
      (node (ref "J1") (pin "2") (pinfunction "2_2") (pintype "passive"))
      (node (ref "J1") (pin "3") (pinfunction "3_3") (pintype "passive"))
      (node (ref "J1") (pin "4") (pinfunction "4_4") (pintype "passive"))
      (node (ref "L1") (pin "2") (pinfunction "2_2") (pintype "passive"))
      (node (ref "M3") (pin "15") (pinfunction "ACIN5V_15") (pintype "passive"))
      (node (ref "M3") (pin "16") (pinfunction "ACIN5V_16") (pintype "passive"))
    )
    (net (code "94") (name "AVDD-CSI") (class "Default")
      (node (ref "C18") (pin "1") (pinfunction "1_1") (pintype "passive"))
      (node (ref "J2") (pin "4") (pinfunction "4_4") (pintype "passive"))
      (node (ref "M3") (pin "8") (pinfunction "AVDD-CSI_8") (pintype "passive"))
    )
    (net (code "95") (name "DC5V") (class "Default")
      (node (ref "C10") (pin "2") (pinfunction "2_2") (pintype "passive"))
      (node (ref "C2") (pin "1") (pinfunction "1_1") (pintype "passive"))
      (node (ref "C28") (pin "1") (pinfunction "1_1") (pintype "passive"))
      (node (ref "C3") (pin "2") (pinfunction "2_2") (pintype "passive"))
      (node (ref "C31") (pin "2") (pinfunction "2_2") (pintype "passive"))
      (node (ref "C32") (pin "1") (pinfunction "1_1") (pintype "passive"))
      (node (ref "C33") (pin "1") (pinfunction "1_1") (pintype "passive"))
      (node (ref "C4") (pin "2") (pinfunction "2_2") (pintype "passive"))
      (node (ref "C49") (pin "2") (pinfunction "2_2") (pintype "passive"))
      (node (ref "C8") (pin "1") (pinfunction "1_1") (pintype "passive"))
      (node (ref "C9") (pin "2") (pinfunction "2_2") (pintype "passive"))
      (node (ref "J7") (pin "2") (pinfunction "2_2") (pintype "passive"))
      (node (ref "L1") (pin "1") (pinfunction "1_1") (pintype "passive"))
      (node (ref "R14") (pin "2") (pinfunction "2_2") (pintype "passive"))
      (node (ref "R4") (pin "2") (pinfunction "2_2") (pintype "passive"))
      (node (ref "U1") (pin "8") (pinfunction "VO_8") (pintype "output"))
      (node (ref "U2") (pin "8") (pinfunction "VO_8") (pintype "output"))
      (node (ref "U4") (pin "5") (pinfunction "VDD_5") (pintype "passive"))
      (node (ref "U5") (pin "5") (pinfunction "IN_5") (pintype "input"))
      (node (ref "U7") (pin "5") (pinfunction "IN_5") (pintype "input"))
    )
    (net (code "96") (name "DOVDD-CSI") (class "Default")
      (node (ref "C13") (pin "1") (pinfunction "1_1") (pintype "passive"))
      (node (ref "C14") (pin "1") (pinfunction "1_1") (pintype "passive"))
      (node (ref "C15") (pin "1") (pinfunction "1_1") (pintype "passive"))
      (node (ref "J2") (pin "11") (pinfunction "11_11") (pintype "passive"))
      (node (ref "M3") (pin "2") (pinfunction "DOVDD-CSI_2") (pintype "passive"))
      (node (ref "M3") (pin "79") (pinfunction "PE16_CSI-RST-F_79") (pintype "passive"))
      (node (ref "R3") (pin "1") (pinfunction "1_1") (pintype "passive"))
      (node (ref "R5") (pin "2") (pinfunction "2_2") (pintype "passive"))
    )
    (net (code "97") (name "DVDD1V8-CSI") (class "Default")
      (node (ref "C17") (pin "1") (pinfunction "1_1") (pintype "passive"))
      (node (ref "J2") (pin "10") (pinfunction "10_10") (pintype "passive"))
      (node (ref "M3") (pin "13") (pinfunction "DVDD1V8-CSI_13") (pintype "passive"))
    )
    (net (code "98") (name "GND") (class "Default")
      (node (ref "ANT1") (pin "2") (pinfunction "2_2") (pintype "passive"))
      (node (ref "ANT1") (pin "3") (pinfunction "3_3") (pintype "passive"))
      (node (ref "C1") (pin "2") (pinfunction "2_2") (pintype "passive"))
      (node (ref "C10") (pin "1") (pinfunction "1_1") (pintype "passive"))
      (node (ref "C11") (pin "1") (pinfunction "1_1") (pintype "passive"))
      (node (ref "C12") (pin "2") (pinfunction "2_2") (pintype "passive"))
      (node (ref "C13") (pin "2") (pinfunction "2_2") (pintype "passive"))
      (node (ref "C14") (pin "2") (pinfunction "2_2") (pintype "passive"))
      (node (ref "C15") (pin "2") (pinfunction "2_2") (pintype "passive"))
      (node (ref "C16") (pin "1") (pinfunction "1_1") (pintype "passive"))
      (node (ref "C17") (pin "2") (pinfunction "2_2") (pintype "passive"))
      (node (ref "C18") (pin "2") (pinfunction "2_2") (pintype "passive"))
      (node (ref "C19") (pin "1") (pinfunction "1_1") (pintype "passive"))
      (node (ref "C2") (pin "2") (pinfunction "2_2") (pintype "passive"))
      (node (ref "C20") (pin "2") (pinfunction "2_2") (pintype "passive"))
      (node (ref "C21") (pin "2") (pinfunction "2_2") (pintype "passive"))
      (node (ref "C22") (pin "1") (pinfunction "1_1") (pintype "passive"))
      (node (ref "C23") (pin "2") (pinfunction "2_2") (pintype "passive"))
      (node (ref "C26") (pin "2") (pinfunction "2_2") (pintype "passive"))
      (node (ref "C28") (pin "2") (pinfunction "2_2") (pintype "passive"))
      (node (ref "C29") (pin "2") (pinfunction "2_2") (pintype "passive"))
      (node (ref "C3") (pin "1") (pinfunction "1_1") (pintype "passive"))
      (node (ref "C30") (pin "2") (pinfunction "2_2") (pintype "passive"))
      (node (ref "C31") (pin "1") (pinfunction "1_1") (pintype "passive"))
      (node (ref "C32") (pin "2") (pinfunction "2_2") (pintype "passive"))
      (node (ref "C33") (pin "2") (pinfunction "2_2") (pintype "passive"))
      (node (ref "C34") (pin "2") (pinfunction "2_2") (pintype "passive"))
      (node (ref "C35") (pin "2") (pinfunction "2_2") (pintype "passive"))
      (node (ref "C36") (pin "2") (pinfunction "2_2") (pintype "passive"))
      (node (ref "C39") (pin "1") (pinfunction "1_1") (pintype "passive"))
      (node (ref "C4") (pin "1") (pinfunction "1_1") (pintype "passive"))
      (node (ref "C40") (pin "1") (pinfunction "1_1") (pintype "passive"))
      (node (ref "C42") (pin "2") (pinfunction "2_2") (pintype "passive"))
      (node (ref "C43") (pin "2") (pinfunction "2_2") (pintype "passive"))
      (node (ref "C44") (pin "2") (pinfunction "2_2") (pintype "passive"))
      (node (ref "C45") (pin "2") (pinfunction "2_2") (pintype "passive"))
      (node (ref "C46") (pin "1") (pinfunction "1_1") (pintype "passive"))
      (node (ref "C47") (pin "1") (pinfunction "1_1") (pintype "passive"))
      (node (ref "C48") (pin "1") (pinfunction "1_1") (pintype "passive"))
      (node (ref "C49") (pin "1") (pinfunction "1_1") (pintype "passive"))
      (node (ref "C5") (pin "1") (pinfunction "1_1") (pintype "passive"))
      (node (ref "C50") (pin "2") (pinfunction "2_2") (pintype "passive"))
      (node (ref "C51") (pin "2") (pinfunction "2_2") (pintype "passive"))
      (node (ref "C52") (pin "2") (pinfunction "2_2") (pintype "passive"))
      (node (ref "C6") (pin "2") (pinfunction "2_2") (pintype "passive"))
      (node (ref "C7") (pin "2") (pinfunction "2_2") (pintype "passive"))
      (node (ref "C8") (pin "2") (pinfunction "2_2") (pintype "passive"))
      (node (ref "C9") (pin "1") (pinfunction "1_1") (pintype "passive"))
      (node (ref "D1") (pin "2") (pinfunction "K_2") (pintype "passive"))
      (node (ref "D2") (pin "2") (pinfunction "K_2") (pintype "passive"))
      (node (ref "D4") (pin "1") (pinfunction "A_1") (pintype "passive"))
      (node (ref "D5") (pin "1") (pinfunction "A_1") (pintype "passive"))
      (node (ref "J1") (pin "34") (pinfunction "34_34") (pintype "passive"))
      (node (ref "J1") (pin "41") (pinfunction "41_41") (pintype "passive"))
      (node (ref "J1") (pin "42") (pinfunction "42_42") (pintype "passive"))
      (node (ref "J1") (pin "5") (pinfunction "5_5") (pintype "passive"))
      (node (ref "J1") (pin "6") (pinfunction "6_6") (pintype "passive"))
      (node (ref "J1") (pin "9") (pinfunction "9_9") (pintype "passive"))
      (node (ref "J10") (pin "1") (pinfunction "0_1") (pintype "passive"))
      (node (ref "J11") (pin "2") (pinfunction "2_2") (pintype "passive"))
      (node (ref "J12") (pin "3") (pinfunction "3_3") (pintype "passive"))
      (node (ref "J13") (pin "3") (pinfunction "3_3") (pintype "passive"))
      (node (ref "J14") (pin "1") (pinfunction "1_1") (pintype "passive"))
      (node (ref "J15") (pin "1") (pinfunction "1_1") (pintype "passive"))
      (node (ref "J16") (pin "3") (pinfunction "3_3") (pintype "passive"))
      (node (ref "J17") (pin "25") (pinfunction "25_25") (pintype "passive"))
      (node (ref "J17") (pin "26") (pinfunction "B13_26") (pintype "passive"))
      (node (ref "J17") (pin "27") (pinfunction "B14_27") (pintype "passive"))
      (node (ref "J17") (pin "28") (pinfunction "B15_28") (pintype "passive"))
      (node (ref "J17") (pin "29") (pinfunction "B16_29") (pintype "passive"))
      (node (ref "J17") (pin "30") (pinfunction "B17_30") (pintype "passive"))
      (node (ref "J17") (pin "31") (pinfunction "B18_31") (pintype "passive"))
      (node (ref "J17") (pin "32") (pinfunction "B13_32") (pintype "passive"))
      (node (ref "J17") (pin "A1") (pinfunction "GND_A1") (pintype "passive"))
      (node (ref "J17") (pin "A12") (pinfunction "GND_A12") (pintype "passive"))
      (node (ref "J17") (pin "B1") (pinfunction "GND_B1") (pintype "passive"))
      (node (ref "J17") (pin "B12") (pinfunction "GND_B12") (pintype "passive"))
      (node (ref "J18") (pin "2") (pinfunction "2_2") (pintype "passive"))
      (node (ref "J19") (pin "2") (pinfunction "2_2") (pintype "passive"))
      (node (ref "J2") (pin "15") (pinfunction "15_15") (pintype "passive"))
      (node (ref "J2") (pin "2") (pinfunction "2_2") (pintype "passive"))
      (node (ref "J2") (pin "25") (pinfunction "25_25") (pintype "passive"))
      (node (ref "J2") (pin "26") (pinfunction "26_26") (pintype "passive"))
      (node (ref "J3") (pin "3") (pinfunction "3_3") (pintype "passive"))
      (node (ref "J5") (pin "4") (pinfunction "4_4") (pintype "passive"))
      (node (ref "J6") (pin "10") (pinfunction "SW1_10") (pintype "passive"))
      (node (ref "J6") (pin "11") (pinfunction "11_11") (pintype "passive"))
      (node (ref "J6") (pin "12") (pinfunction "12_12") (pintype "passive"))
      (node (ref "J6") (pin "13") (pinfunction "13_13") (pintype "passive"))
      (node (ref "J6") (pin "6") (pinfunction "VSS_6") (pintype "passive"))
      (node (ref "J7") (pin "1") (pinfunction "1_1") (pintype "passive"))
      (node (ref "J8") (pin "3") (pinfunction "3_3") (pintype "passive"))
      (node (ref "J8") (pin "4") (pinfunction "4_4") (pintype "passive"))
      (node (ref "J9") (pin "3") (pinfunction "3_3") (pintype "passive"))
      (node (ref "J9") (pin "4") (pinfunction "4_4") (pintype "passive"))
      (node (ref "M3") (pin "103") (pinfunction "GND_103") (pintype "passive"))
      (node (ref "M3") (pin "121") (pinfunction "GND_121") (pintype "passive"))
      (node (ref "M3") (pin "122") (pinfunction "GND_122") (pintype "passive"))
      (node (ref "M3") (pin "123") (pinfunction "GND_123") (pintype "passive"))
      (node (ref "M3") (pin "124") (pinfunction "GND_124") (pintype "passive"))
      (node (ref "M3") (pin "40") (pinfunction "GND_40") (pintype "passive"))
      (node (ref "M3") (pin "51") (pinfunction "GND_51") (pintype "passive"))
      (node (ref "M3") (pin "9") (pinfunction "GND_9") (pintype "passive"))
      (node (ref "R16") (pin "1") (pinfunction "1_1") (pintype "passive"))
      (node (ref "R2") (pin "1") (pinfunction "1_1") (pintype "passive"))
      (node (ref "R33") (pin "2") (pinfunction "2_2") (pintype "passive"))
      (node (ref "R37") (pin "1") (pinfunction "1_1") (pintype "passive"))
      (node (ref "R38") (pin "2") (pinfunction "2_2") (pintype "passive"))
      (node (ref "R39") (pin "2") (pinfunction "2_2") (pintype "passive"))
      (node (ref "R41") (pin "2") (pinfunction "2_2") (pintype "passive"))
      (node (ref "R45") (pin "2") (pinfunction "2_2") (pintype "passive"))
      (node (ref "R59") (pin "1") (pinfunction "1_1") (pintype "passive"))
      (node (ref "R60") (pin "1") (pinfunction "1_1") (pintype "passive"))
      (node (ref "R63") (pin "2") (pinfunction "2_2") (pintype "passive"))
      (node (ref "R64") (pin "2") (pinfunction "2_2") (pintype "passive"))
      (node (ref "R9") (pin "1") (pinfunction "1_1") (pintype "passive"))
      (node (ref "S1") (pin "1") (pinfunction "1_1") (pintype "passive"))
      (node (ref "U2") (pin "5") (pinfunction "GND_5") (pintype "power_in"))
      (node (ref "U3") (pin "2") (pinfunction "GND_2") (pintype "passive"))
      (node (ref "U4") (pin "8") (pinfunction "GND_8") (pintype "passive"))
      (node (ref "U5") (pin "2") (pinfunction "GND_2") (pintype "power_in"))
      (node (ref "U6") (pin "1") (pinfunction "GND_1") (pintype "passive"))
      (node (ref "U6") (pin "20") (pinfunction "GND_20") (pintype "passive"))
      (node (ref "U6") (pin "3") (pinfunction "GND_3") (pintype "passive"))
      (node (ref "U6") (pin "31") (pinfunction "GND_31") (pintype "passive"))
      (node (ref "U6") (pin "33") (pinfunction "GND_33") (pintype "passive"))
      (node (ref "U6") (pin "36") (pinfunction "GND_36") (pintype "passive"))
      (node (ref "U7") (pin "2") (pinfunction "GND_2") (pintype "power_in"))
      (node (ref "Y1") (pin "2") (pinfunction "GND_2") (pintype "passive"))
      (node (ref "Y1") (pin "4") (pinfunction "GND_4") (pintype "passive"))
    )
    (net (code "99") (name "HOST2_5V") (class "Default")
      (node (ref "C50") (pin "1") (pinfunction "1_1") (pintype "passive"))
      (node (ref "C52") (pin "1") (pinfunction "1_1") (pintype "passive"))
      (node (ref "J5") (pin "1") (pinfunction "1_1") (pintype "passive"))
      (node (ref "U7") (pin "1") (pinfunction "VOUT1_1") (pintype "output"))
    )
    (net (code "100") (name "Net-(ANT1-W)") (class "Default")
      (node (ref "ANT1") (pin "1") (pinfunction "W_1") (pintype "passive"))
      (node (ref "C39") (pin "2") (pinfunction "2_2") (pintype "passive"))
      (node (ref "C41") (pin "2") (pinfunction "2_2") (pintype "passive"))
    )
    (net (code "101") (name "Net-(C1-Pad1)") (class "Default")
      (node (ref "C1") (pin "1") (pinfunction "1_1") (pintype "passive"))
      (node (ref "R1") (pin "1") (pinfunction "1_1") (pintype "passive"))
    )
    (net (code "102") (name "Net-(C7-Pad1)") (class "Default")
      (node (ref "C7") (pin "1") (pinfunction "1_1") (pintype "passive"))
      (node (ref "R8") (pin "1") (pinfunction "1_1") (pintype "passive"))
    )
    (net (code "103") (name "Net-(C23-Pad1)") (class "Default")
      (node (ref "C23") (pin "1") (pinfunction "1_1") (pintype "passive"))
      (node (ref "J9") (pin "1") (pinfunction "1_1") (pintype "passive"))
      (node (ref "L2") (pin "1") (pinfunction "1_1") (pintype "passive"))
    )
    (net (code "104") (name "Net-(C25-Pad2)") (class "Default")
      (node (ref "C25") (pin "2") (pinfunction "2_2") (pintype "passive"))
      (node (ref "R29") (pin "1") (pinfunction "1_1") (pintype "passive"))
    )
    (net (code "105") (name "Net-(C27-Pad2)") (class "Default")
      (node (ref "C27") (pin "2") (pinfunction "2_2") (pintype "passive"))
      (node (ref "R30") (pin "1") (pinfunction "1_1") (pintype "passive"))
    )
    (net (code "106") (name "Net-(C29-Pad1)") (class "Default")
      (node (ref "C29") (pin "1") (pinfunction "1_1") (pintype "passive"))
      (node (ref "J9") (pin "2") (pinfunction "2_2") (pintype "passive"))
      (node (ref "L3") (pin "1") (pinfunction "1_1") (pintype "passive"))
    )
    (net (code "107") (name "Net-(C37-Pad2)") (class "Default")
      (node (ref "C37") (pin "2") (pinfunction "2_2") (pintype "passive"))
      (node (ref "J12") (pin "1") (pinfunction "1_1") (pintype "passive"))
      (node (ref "J13") (pin "1") (pinfunction "1_1") (pintype "passive"))
    )
    (net (code "108") (name "Net-(C38-Pad2)") (class "Default")
      (node (ref "C38") (pin "2") (pinfunction "2_2") (pintype "passive"))
      (node (ref "J12") (pin "4") (pinfunction "4_4") (pintype "passive"))
      (node (ref "J13") (pin "4") (pinfunction "4_4") (pintype "passive"))
    )
    (net (code "109") (name "Net-(D3-PadK)") (class "Default")
      (node (ref "D3") (pin "K") (pinfunction "K_K") (pintype "passive"))
      (node (ref "R35") (pin "1") (pinfunction "1_1") (pintype "passive"))
    )
    (net (code "110") (name "Net-(D4-K)") (class "Default")
      (node (ref "D4") (pin "2") (pinfunction "K_2") (pintype "passive"))
      (node (ref "J17") (pin "A7") (pinfunction "D-_A7") (pintype "passive"))
      (node (ref "J17") (pin "B7") (pinfunction "D--_B7") (pintype "passive"))
      (node (ref "R49") (pin "2") (pinfunction "2_2") (pintype "passive"))
    )
    (net (code "111") (name "Net-(D5-K)") (class "Default")
      (node (ref "D5") (pin "2") (pinfunction "K_2") (pintype "passive"))
      (node (ref "J17") (pin "A6") (pinfunction "D+_A6") (pintype "passive"))
      (node (ref "J17") (pin "B6") (pinfunction "D++_B6") (pintype "passive"))
      (node (ref "R47") (pin "2") (pinfunction "2_2") (pintype "passive"))
    )
    (net (code "112") (name "Net-(J2-Pad6)") (class "Default")
      (node (ref "J2") (pin "6") (pinfunction "6_6") (pintype "passive"))
      (node (ref "R3") (pin "2") (pinfunction "2_2") (pintype "passive"))
    )
    (net (code "113") (name "Net-(J3-Pad1)") (class "Default")
      (node (ref "J3") (pin "1") (pinfunction "1_1") (pintype "passive"))
      (node (ref "R12") (pin "2") (pinfunction "2_2") (pintype "passive"))
    )
    (net (code "114") (name "Net-(J3-Pad2)") (class "Default")
      (node (ref "J3") (pin "2") (pinfunction "2_2") (pintype "passive"))
      (node (ref "R11") (pin "2") (pinfunction "2_2") (pintype "passive"))
    )
    (net (code "115") (name "Net-(J6-CLK)") (class "Default")
      (node (ref "J6") (pin "5") (pinfunction "CLK_5") (pintype "bidirectional"))
      (node (ref "R24") (pin "2") (pinfunction "2_2") (pintype "passive"))
    )
    (net (code "116") (name "Net-(J16-Pad1)") (class "Default")
      (node (ref "J16") (pin "1") (pinfunction "1_1") (pintype "passive"))
      (node (ref "R44") (pin "2") (pinfunction "2_2") (pintype "passive"))
    )
    (net (code "117") (name "Net-(J16-Pad2)") (class "Default")
      (node (ref "J16") (pin "2") (pinfunction "2_2") (pintype "passive"))
      (node (ref "R43") (pin "2") (pinfunction "2_2") (pintype "passive"))
    )
    (net (code "118") (name "Net-(J18-Pad1)") (class "Default")
      (node (ref "J18") (pin "1") (pinfunction "1_1") (pintype "passive"))
      (node (ref "R56") (pin "2") (pinfunction "2_2") (pintype "passive"))
    )
    (net (code "119") (name "Net-(L11-Pad2)") (class "Default")
      (node (ref "L11") (pin "2") (pinfunction "2_2") (pintype "passive"))
      (node (ref "R1") (pin "2") (pinfunction "2_2") (pintype "passive"))
      (node (ref "U1") (pin "1") (pinfunction "LX_1") (pintype "passive"))
      (node (ref "U1") (pin "2") (pinfunction "LX_2") (pintype "passive"))
    )
    (net (code "120") (name "Net-(L12-Pad2)") (class "Default")
      (node (ref "L12") (pin "2") (pinfunction "2_2") (pintype "passive"))
      (node (ref "R8") (pin "2") (pinfunction "2_2") (pintype "passive"))
      (node (ref "U2") (pin "1") (pinfunction "LX_1") (pintype "passive"))
      (node (ref "U2") (pin "2") (pinfunction "LX_2") (pintype "passive"))
    )
    (net (code "121") (name "Net-(M3-PA-SHDN{slash}PH9)") (class "Default")
      (node (ref "M3") (pin "39") (pinfunction "PA-SHDN/PH9_39") (pintype "passive"))
      (node (ref "R17") (pin "2") (pinfunction "2_2") (pintype "passive"))
    )
    (net (code "122") (name "Net-(M3-UART2-RX{slash}PB1)") (class "Default")
      (node (ref "M3") (pin "23") (pinfunction "UART2-RX/PB1_23") (pintype "passive"))
      (node (ref "R11") (pin "1") (pinfunction "1_1") (pintype "passive"))
    )
    (net (code "123") (name "Net-(M3-UART2-TX{slash}PB0)") (class "Default")
      (node (ref "M3") (pin "24") (pinfunction "UART2-TX/PB0_24") (pintype "passive"))
      (node (ref "R12") (pin "1") (pinfunction "1_1") (pintype "passive"))
    )
    (net (code "124") (name "Net-(U1-EN)") (class "Default")
      (node (ref "C6") (pin "1") (pinfunction "1_1") (pintype "passive"))
      (node (ref "R6") (pin "1") (pinfunction "1_1") (pintype "passive"))
      (node (ref "U1") (pin "4") (pinfunction "EN_4") (pintype "passive"))
    )
    (net (code "125") (name "Net-(U1-FB)") (class "Default")
      (node (ref "R4") (pin "1") (pinfunction "1_1") (pintype "passive"))
      (node (ref "R7") (pin "2") (pinfunction "2_2") (pintype "passive"))
      (node (ref "U1") (pin "6") (pinfunction "FB_6") (pintype "passive"))
    )
    (net (code "126") (name "Net-(U1-GND)") (class "Default")
      (node (ref "R7") (pin "1") (pinfunction "1_1") (pintype "passive"))
      (node (ref "U1") (pin "5") (pinfunction "GND_5") (pintype "power_in"))
    )
    (net (code "127") (name "Net-(U1-OC)") (class "Default")
      (node (ref "R2") (pin "2") (pinfunction "2_2") (pintype "passive"))
      (node (ref "U1") (pin "7") (pinfunction "OC_7") (pintype "passive"))
    )
    (net (code "128") (name "Net-(U2-EN)") (class "Default")
      (node (ref "C12") (pin "1") (pinfunction "1_1") (pintype "passive"))
      (node (ref "R15") (pin "1") (pinfunction "1_1") (pintype "passive"))
      (node (ref "U2") (pin "4") (pinfunction "EN_4") (pintype "passive"))
    )
    (net (code "129") (name "Net-(U2-FB)") (class "Default")
      (node (ref "R14") (pin "1") (pinfunction "1_1") (pintype "passive"))
      (node (ref "R16") (pin "2") (pinfunction "2_2") (pintype "passive"))
      (node (ref "U2") (pin "6") (pinfunction "FB_6") (pintype "passive"))
    )
    (net (code "130") (name "Net-(U2-OC)") (class "Default")
      (node (ref "R9") (pin "2") (pinfunction "2_2") (pintype "passive"))
      (node (ref "U2") (pin "7") (pinfunction "OC_7") (pintype "passive"))
    )
    (net (code "131") (name "Net-(U3-IN_A1)") (class "Default")
      (node (ref "R25") (pin "1") (pinfunction "1_1") (pintype "passive"))
      (node (ref "R28") (pin "2") (pinfunction "2_2") (pintype "passive"))
      (node (ref "U3") (pin "1") (pinfunction "IN_A1_1") (pintype "passive"))
      (node (ref "U3") (pin "4") (pinfunction "OUT_Y2_4") (pintype "passive"))
    )
    (net (code "132") (name "Net-(U3-IN_A2)") (class "Default")
      (node (ref "C30") (pin "1") (pinfunction "1_1") (pintype "passive"))
      (node (ref "R28") (pin "1") (pinfunction "1_1") (pintype "passive"))
      (node (ref "U3") (pin "3") (pinfunction "IN_A2_3") (pintype "passive"))
      (node (ref "Y1") (pin "3") (pinfunction "XO_3") (pintype "passive"))
    )
    (net (code "133") (name "Net-(U3-OUT_Y1)") (class "Default")
      (node (ref "R26") (pin "2") (pinfunction "2_2") (pintype "passive"))
      (node (ref "U3") (pin "6") (pinfunction "OUT_Y1_6") (pintype "passive"))
    )
    (net (code "134") (name "Net-(U3-VCC)") (class "Default")
      (node (ref "R27") (pin "2") (pinfunction "2_2") (pintype "passive"))
      (node (ref "U3") (pin "5") (pinfunction "VCC_5") (pintype "passive"))
    )
    (net (code "135") (name "Net-(U4-IN+)") (class "Default")
      (node (ref "R29") (pin "2") (pinfunction "2_2") (pintype "passive"))
      (node (ref "U4") (pin "3") (pinfunction "IN+_3") (pintype "passive"))
    )
    (net (code "136") (name "Net-(U4-IN-)") (class "Default")
      (node (ref "R30") (pin "2") (pinfunction "2_2") (pintype "passive"))
      (node (ref "U4") (pin "4") (pinfunction "IN-_4") (pintype "passive"))
    )
    (net (code "137") (name "Net-(U4-OUT+)") (class "Default")
      (node (ref "L2") (pin "2") (pinfunction "2_2") (pintype "passive"))
      (node (ref "U4") (pin "7") (pinfunction "OUT+_7") (pintype "passive"))
    )
    (net (code "138") (name "Net-(U4-OUT-)") (class "Default")
      (node (ref "L3") (pin "2") (pinfunction "2_2") (pintype "passive"))
      (node (ref "U4") (pin "6") (pinfunction "OUT-_6") (pintype "passive"))
    )
    (net (code "139") (name "Net-(U5-EN)") (class "Default")
      (node (ref "R58") (pin "1") (pinfunction "1_1") (pintype "passive"))
      (node (ref "R59") (pin "2") (pinfunction "2_2") (pintype "passive"))
      (node (ref "U5") (pin "4") (pinfunction "EN_4") (pintype "passive"))
    )
    (net (code "140") (name "Net-(U5-FLAG)") (class "Default")
      (node (ref "R60") (pin "2") (pinfunction "2_2") (pintype "passive"))
      (node (ref "U5") (pin "3") (pinfunction "FLAG_3") (pintype "passive"))
    )
    (net (code "141") (name "Net-(U6-LPO)") (class "Default")
      (node (ref "R40") (pin "1") (pinfunction "1_1") (pintype "passive"))
      (node (ref "U6") (pin "24") (pinfunction "LPO_24") (pintype "passive"))
    )
    (net (code "142") (name "Net-(U6-SDIO_DATA_CLK)") (class "Default")
      (node (ref "R48") (pin "1") (pinfunction "1_1") (pintype "passive"))
      (node (ref "U6") (pin "17") (pinfunction "SDIO_DATA_CLK_17") (pintype "passive"))
    )
    (net (code "143") (name "Net-(U6-VIN_LDO)") (class "Default")
      (node (ref "C48") (pin "2") (pinfunction "2_2") (pintype "passive"))
      (node (ref "L4") (pin "2") (pinfunction "2_2") (pintype "passive"))
      (node (ref "U6") (pin "23") (pinfunction "VIN_LDO_23") (pintype "passive"))
    )
    (net (code "144") (name "Net-(U6-VIN_LDO_OUT)") (class "Default")
      (node (ref "L4") (pin "1") (pinfunction "1_1") (pintype "passive"))
      (node (ref "U6") (pin "21") (pinfunction "VIN_LDO_OUT_21") (pintype "passive"))
    )
    (net (code "145") (name "Net-(U6-WL_BT_ANT)") (class "Default")
      (node (ref "C40") (pin "2") (pinfunction "2_2") (pintype "passive"))
      (node (ref "C41") (pin "1") (pinfunction "1_1") (pintype "passive"))
      (node (ref "U6") (pin "2") (pinfunction "WL_BT_ANT_2") (pintype "passive"))
    )
    (net (code "146") (name "Net-(U6-WL_VDD_TCXO)") (class "Default")
      (node (ref "R36") (pin "1") (pinfunction "1_1") (pintype "passive"))
      (node (ref "U6") (pin "29") (pinfunction "WL_VDD_TCXO_29") (pintype "passive"))
    )
    (net (code "147") (name "Net-(U7-EN)") (class "Default")
      (node (ref "R62") (pin "1") (pinfunction "1_1") (pintype "passive"))
      (node (ref "R64") (pin "1") (pinfunction "1_1") (pintype "passive"))
      (node (ref "U7") (pin "4") (pinfunction "EN_4") (pintype "passive"))
    )
    (net (code "148") (name "Net-(U7-FLAG)") (class "Default")
      (node (ref "R63") (pin "1") (pinfunction "1_1") (pintype "passive"))
      (node (ref "U7") (pin "3") (pinfunction "FLAG_3") (pintype "passive"))
    )
    (net (code "149") (name "Net-(Y1-XI)") (class "Default")
      (node (ref "C21") (pin "1") (pinfunction "1_1") (pintype "passive"))
      (node (ref "R25") (pin "2") (pinfunction "2_2") (pintype "passive"))
      (node (ref "Y1") (pin "1") (pinfunction "XI_1") (pintype "passive"))
    )
    (net (code "150") (name "PS") (class "Default")
      (node (ref "C11") (pin "2") (pinfunction "2_2") (pintype "passive"))
      (node (ref "D3") (pin "A") (pinfunction "A_A") (pintype "passive"))
      (node (ref "J19") (pin "3") (pinfunction "3_3") (pintype "passive"))
      (node (ref "J4") (pin "3") (pinfunction "3_3") (pintype "passive"))
      (node (ref "L12") (pin "1") (pinfunction "1_1") (pintype "passive"))
      (node (ref "M3") (pin "10") (pinfunction "PS_10") (pintype "passive"))
      (node (ref "M3") (pin "11") (pinfunction "PS_11") (pintype "passive"))
      (node (ref "U2") (pin "3") (pinfunction "VIN_3") (pintype "input"))
    )
    (net (code "151") (name "USBVBUS") (class "Default")
      (node (ref "C34") (pin "1") (pinfunction "1_1") (pintype "passive"))
      (node (ref "C44") (pin "1") (pinfunction "1_1") (pintype "passive"))
      (node (ref "C45") (pin "1") (pinfunction "1_1") (pintype "passive"))
      (node (ref "C46") (pin "2") (pinfunction "2_2") (pintype "passive"))
      (node (ref "J17") (pin "A4") (pinfunction "VBUS_A4") (pintype "passive"))
      (node (ref "J17") (pin "A9") (pinfunction "VBUS_A9") (pintype "passive"))
      (node (ref "J17") (pin "B4") (pinfunction "VBUS_B4") (pintype "passive"))
      (node (ref "J17") (pin "B9") (pinfunction "VBUS_B9") (pintype "passive"))
      (node (ref "M3") (pin "12") (pinfunction "USBVBUS_12") (pintype "passive"))
      (node (ref "R55") (pin "2") (pinfunction "2_2") (pintype "passive"))
      (node (ref "R57") (pin "1") (pinfunction "1_1") (pintype "passive"))
      (node (ref "U5") (pin "1") (pinfunction "VOUT1_1") (pintype "output"))
    )
    (net (code "152") (name "VBAT") (class "Default")
      (node (ref "C35") (pin "1") (pinfunction "1_1") (pintype "passive"))
      (node (ref "C36") (pin "1") (pinfunction "1_1") (pintype "passive"))
      (node (ref "J10") (pin "3") (pinfunction "2_3") (pintype "passive"))
      (node (ref "J11") (pin "1") (pinfunction "1_1") (pintype "passive"))
      (node (ref "J4") (pin "1") (pinfunction "1_1") (pintype "passive"))
      (node (ref "M3") (pin "19") (pinfunction "VBAT_19") (pintype "passive"))
      (node (ref "M3") (pin "20") (pinfunction "VBAT_20") (pintype "passive"))
    )
    (net (code "153") (name "VCC") (class "Default")
      (node (ref "C5") (pin "2") (pinfunction "2_2") (pintype "passive"))
      (node (ref "J14") (pin "2") (pinfunction "2_2") (pintype "passive"))
      (node (ref "J15") (pin "2") (pinfunction "2_2") (pintype "passive"))
      (node (ref "J4") (pin "2") (pinfunction "2_2") (pintype "passive"))
      (node (ref "L11") (pin "1") (pinfunction "1_1") (pintype "passive"))
      (node (ref "R38") (pin "1") (pinfunction "1_1") (pintype "passive"))
      (node (ref "R41") (pin "1") (pinfunction "1_1") (pintype "passive"))
      (node (ref "U1") (pin "3") (pinfunction "VIN_3") (pintype "input"))
    )
    (net (code "154") (name "VCC-3V0") (class "Default")
      (node (ref "C16") (pin "2") (pinfunction "2_2") (pintype "passive"))
      (node (ref "C19") (pin "2") (pinfunction "2_2") (pintype "passive"))
      (node (ref "J6") (pin "4") (pinfunction "VDD_4") (pintype "power_in"))
      (node (ref "M3") (pin "1") (pinfunction "VCC-3V0_1") (pintype "passive"))
      (node (ref "R15") (pin "2") (pinfunction "2_2") (pintype "passive"))
      (node (ref "R17") (pin "1") (pinfunction "1_1") (pintype "passive"))
      (node (ref "R18") (pin "2") (pinfunction "2_2") (pintype "passive"))
      (node (ref "R19") (pin "2") (pinfunction "2_2") (pintype "passive"))
      (node (ref "R20") (pin "2") (pinfunction "2_2") (pintype "passive"))
      (node (ref "R21") (pin "2") (pinfunction "2_2") (pintype "passive"))
      (node (ref "R22") (pin "2") (pinfunction "2_2") (pintype "passive"))
      (node (ref "R23") (pin "2") (pinfunction "2_2") (pintype "passive"))
      (node (ref "R34") (pin "2") (pinfunction "2_2") (pintype "passive"))
      (node (ref "R46") (pin "1") (pinfunction "1_1") (pintype "passive"))
      (node (ref "R57") (pin "2") (pinfunction "2_2") (pintype "passive"))
      (node (ref "R6") (pin "2") (pinfunction "2_2") (pintype "passive"))
      (node (ref "U4") (pin "1") (pinfunction "SD_1") (pintype "passive"))
      (node (ref "U4") (pin "2") (pinfunction "ABD_2") (pintype "passive"))
    )
    (net (code "155") (name "VCC-CTP") (class "Default")
      (node (ref "J1") (pin "35") (pinfunction "35_35") (pintype "passive"))
      (node (ref "J1") (pin "36") (pinfunction "36_36") (pintype "passive"))
      (node (ref "M3") (pin "6") (pinfunction "VCC-CTP_6") (pintype "passive"))
      (node (ref "R10") (pin "1") (pinfunction "1_1") (pintype "passive"))
      (node (ref "R13") (pin "1") (pinfunction "1_1") (pintype "passive"))
    )
    (net (code "156") (name "VCC-LCD") (class "Default")
      (node (ref "J1") (pin "7") (pinfunction "7_7") (pintype "passive"))
      (node (ref "J1") (pin "8") (pinfunction "8_8") (pintype "passive"))
      (node (ref "M3") (pin "4") (pinfunction "VCC-LCD_4") (pintype "passive"))
      (node (ref "R61") (pin "2") (pinfunction "2_2") (pintype "passive"))
    )
    (net (code "157") (name "VCC-WIFI") (class "Default")
      (node (ref "C43") (pin "1") (pinfunction "1_1") (pintype "passive"))
      (node (ref "C47") (pin "2") (pinfunction "2_2") (pintype "passive"))
      (node (ref "C51") (pin "1") (pinfunction "1_1") (pintype "passive"))
      (node (ref "M3") (pin "3") (pinfunction "VCC-IO-WIFI_3") (pintype "passive"))
      (node (ref "R27") (pin "1") (pinfunction "1_1") (pintype "passive"))
      (node (ref "R31") (pin "1") (pinfunction "1_1") (pintype "passive"))
      (node (ref "R32") (pin "1") (pinfunction "1_1") (pintype "passive"))
      (node (ref "R36") (pin "2") (pinfunction "2_2") (pintype "passive"))
      (node (ref "R42") (pin "1") (pinfunction "1_1") (pintype "passive"))
      (node (ref "R50") (pin "1") (pinfunction "1_1") (pintype "passive"))
      (node (ref "R51") (pin "1") (pinfunction "1_1") (pintype "passive"))
      (node (ref "R52") (pin "1") (pinfunction "1_1") (pintype "passive"))
      (node (ref "R53") (pin "1") (pinfunction "1_1") (pintype "passive"))
      (node (ref "R54") (pin "1") (pinfunction "1_1") (pintype "passive"))
      (node (ref "U6") (pin "22") (pinfunction "VDDIO_22") (pintype "passive"))
      (node (ref "U6") (pin "9") (pinfunction "VBAT_9") (pintype "passive"))
    )
    (net (code "158") (name "unconnected-(J2-Pad1)") (class "Default")
      (node (ref "J2") (pin "1") (pinfunction "1_1") (pintype "passive"))
    )
    (net (code "159") (name "unconnected-(J2-Pad23)") (class "Default")
      (node (ref "J2") (pin "23") (pinfunction "23_23") (pintype "passive"))
    )
    (net (code "160") (name "unconnected-(J2-Pad24)") (class "Default")
      (node (ref "J2") (pin "24") (pinfunction "24_24") (pintype "passive"))
    )
    (net (code "161") (name "unconnected-(J5-GND-Pad0)") (class "Default")
      (node (ref "J5") (pin "0") (pinfunction "GND_0") (pintype "passive"))
    )
    (net (code "162") (name "unconnected-(J10-1-Pad2)") (class "Default")
      (node (ref "J10") (pin "2") (pinfunction "1_2") (pintype "passive"))
    )
    (net (code "163") (name "unconnected-(J17-CC1-PadA5)") (class "Default")
      (node (ref "J17") (pin "A5") (pinfunction "CC1_A5") (pintype "passive+no_connect"))
    )
    (net (code "164") (name "unconnected-(J17-CC2-PadB5)") (class "Default")
      (node (ref "J17") (pin "B5") (pinfunction "CC2_B5") (pintype "passive+no_connect"))
    )
    (net (code "165") (name "unconnected-(J17-RX1+-PadB11)") (class "Default")
      (node (ref "J17") (pin "B11") (pinfunction "RX1+_B11") (pintype "passive+no_connect"))
    )
    (net (code "166") (name "unconnected-(J17-RX1--PadB10)") (class "Default")
      (node (ref "J17") (pin "B10") (pinfunction "RX1-_B10") (pintype "passive+no_connect"))
    )
    (net (code "167") (name "unconnected-(J17-RX2+-PadA11)") (class "Default")
      (node (ref "J17") (pin "A11") (pinfunction "RX2+_A11") (pintype "passive+no_connect"))
    )
    (net (code "168") (name "unconnected-(J17-RX2--PadA10)") (class "Default")
      (node (ref "J17") (pin "A10") (pinfunction "RX2-_A10") (pintype "passive+no_connect"))
    )
    (net (code "169") (name "unconnected-(J17-SBU1-PadA8)") (class "Default")
      (node (ref "J17") (pin "A8") (pinfunction "SBU1_A8") (pintype "passive+no_connect"))
    )
    (net (code "170") (name "unconnected-(J17-SBU2-PadB8)") (class "Default")
      (node (ref "J17") (pin "B8") (pinfunction "SBU2_B8") (pintype "passive+no_connect"))
    )
    (net (code "171") (name "unconnected-(J17-TX1+-PadA2)") (class "Default")
      (node (ref "J17") (pin "A2") (pinfunction "TX1+_A2") (pintype "passive+no_connect"))
    )
    (net (code "172") (name "unconnected-(J17-TX1--PadA3)") (class "Default")
      (node (ref "J17") (pin "A3") (pinfunction "TX1-_A3") (pintype "passive+no_connect"))
    )
    (net (code "173") (name "unconnected-(J17-TX2+-PadB2)") (class "Default")
      (node (ref "J17") (pin "B2") (pinfunction "TX2+_B2") (pintype "passive+no_connect"))
    )
    (net (code "174") (name "unconnected-(J17-TX2--PadB3)") (class "Default")
      (node (ref "J17") (pin "B3") (pinfunction "TX2-_B3") (pintype "passive+no_connect"))
    )
    (net (code "175") (name "unconnected-(M3-NC-Pad125)") (class "Default")
      (node (ref "M3") (pin "125") (pinfunction "NC_125") (pintype "passive"))
    )
    (net (code "176") (name "unconnected-(M3-NC-Pad126)") (class "Default")
      (node (ref "M3") (pin "126") (pinfunction "NC_126") (pintype "passive"))
    )
    (net (code "177") (name "unconnected-(M3-PE14_CSI-RST-R-Pad77)") (class "Default")
      (node (ref "M3") (pin "77") (pinfunction "PE14_CSI-RST-R_77") (pintype "passive"))
    )
    (net (code "178") (name "unconnected-(M3-PE15_CSI-STBY-R-Pad78)") (class "Default")
      (node (ref "M3") (pin "78") (pinfunction "PE15_CSI-STBY-R_78") (pintype "passive"))
    )
    (net (code "179") (name "unconnected-(M3-PL11-Pad104)") (class "Default")
      (node (ref "M3") (pin "104") (pinfunction "PL11_104") (pintype "passive"))
    )
    (net (code "180") (name "unconnected-(M3-UART2-RTS{slash}PB2-Pad26)") (class "Default")
      (node (ref "M3") (pin "26") (pinfunction "UART2-RTS/PB2_26") (pintype "passive"))
    )
    (net (code "181") (name "unconnected-(M3-UART3-RX{slash}PH7-Pad27)") (class "Default")
      (node (ref "M3") (pin "27") (pinfunction "UART3-RX/PH7_27") (pintype "passive"))
    )
    (net (code "182") (name "unconnected-(M3-UART3-TX{slash}PH6-Pad28)") (class "Default")
      (node (ref "M3") (pin "28") (pinfunction "UART3-TX/PH6_28") (pintype "passive"))
    )
    (net (code "183") (name "unconnected-(M3-VBAT-EXT-Pad17)") (class "Default")
      (node (ref "M3") (pin "17") (pinfunction "VBAT-EXT_17") (pintype "passive"))
    )
    (net (code "184") (name "unconnected-(M3-VBAT-EXT-Pad18)") (class "Default")
      (node (ref "M3") (pin "18") (pinfunction "VBAT-EXT_18") (pintype "passive"))
    )
    (net (code "185") (name "unconnected-(M3-VCC-RTC-Pad7)") (class "Default")
      (node (ref "M3") (pin "7") (pinfunction "VCC-RTC_7") (pintype "passive"))
    )
    (net (code "186") (name "unconnected-(U6-BT_XTAL_IN-Pad37)") (class "Default")
      (node (ref "U6") (pin "37") (pinfunction "BT_XTAL_IN_37") (pintype "passive"))
    )
    (net (code "187") (name "unconnected-(U6-BT_XTAL_OUT-Pad38)") (class "Default")
      (node (ref "U6") (pin "38") (pinfunction "BT_XTAL_OUT_38") (pintype "passive"))
    )
    (net (code "188") (name "unconnected-(U6-NC-Pad4)") (class "Default")
      (node (ref "U6") (pin "4") (pinfunction "NC_4") (pintype "passive"))
    )
    (net (code "189") (name "unconnected-(U6-NC-Pad5)") (class "Default")
      (node (ref "U6") (pin "5") (pinfunction "NC_5") (pintype "passive"))
    )
    (net (code "190") (name "unconnected-(U6-NC-Pad8)") (class "Default")
      (node (ref "U6") (pin "8") (pinfunction "NC_8") (pintype "passive"))
    )
    (net (code "191") (name "unconnected-(U6-NC-Pad10)") (class "Default")
      (node (ref "U6") (pin "10") (pinfunction "NC_10") (pintype "passive"))
    )
    (net (code "192") (name "unconnected-(U6-NC-Pad11)") (class "Default")
      (node (ref "U6") (pin "11") (pinfunction "NC_11") (pintype "passive"))
    )
    (net (code "193") (name "unconnected-(U6-NC-Pad32)") (class "Default")
      (node (ref "U6") (pin "32") (pinfunction "NC_32") (pintype "passive"))
    )
    (net (code "194") (name "unconnected-(U6-NC-Pad35)") (class "Default")
      (node (ref "U6") (pin "35") (pinfunction "NC_35") (pintype "passive"))
    )
    (net (code "195") (name "unconnected-(U6-NC-Pad39)") (class "Default")
      (node (ref "U6") (pin "39") (pinfunction "NC_39") (pintype "passive"))
    )
    (net (code "196") (name "unconnected-(U6-NC-Pad40)") (class "Default")
      (node (ref "U6") (pin "40") (pinfunction "NC_40") (pintype "passive"))
    )
    (net (code "197") (name "unconnected-(U6-NC-Pad45)") (class "Default")
      (node (ref "U6") (pin "45") (pinfunction "NC_45") (pintype "passive"))
    )
    (net (code "198") (name "unconnected-(U6-NC-Pad46)") (class "Default")
      (node (ref "U6") (pin "46") (pinfunction "NC_46") (pintype "passive"))
    )
    (net (code "199") (name "unconnected-(U6-NC-Pad47)") (class "Default")
      (node (ref "U6") (pin "47") (pinfunction "NC_47") (pintype "passive"))
    )
    (net (code "200") (name "unconnected-(U6-PCM_CLK-Pad26)") (class "Default")
      (node (ref "U6") (pin "26") (pinfunction "PCM_CLK_26") (pintype "passive"))
    )
    (net (code "201") (name "unconnected-(U6-PCM_IN-Pad27)") (class "Default")
      (node (ref "U6") (pin "27") (pinfunction "PCM_IN_27") (pintype "passive"))
    )
    (net (code "202") (name "unconnected-(U6-PCM_OUT-Pad25)") (class "Default")
      (node (ref "U6") (pin "25") (pinfunction "PCM_OUT_25") (pintype "passive"))
    )
    (net (code "203") (name "unconnected-(U6-PCM_SYNC-Pad28)") (class "Default")
      (node (ref "U6") (pin "28") (pinfunction "PCM_SYNC_28") (pintype "passive"))
    )
  )
)
